# rack_backplane_v9_0.net
KiCad netlist of a schematic drawn in EAGLE
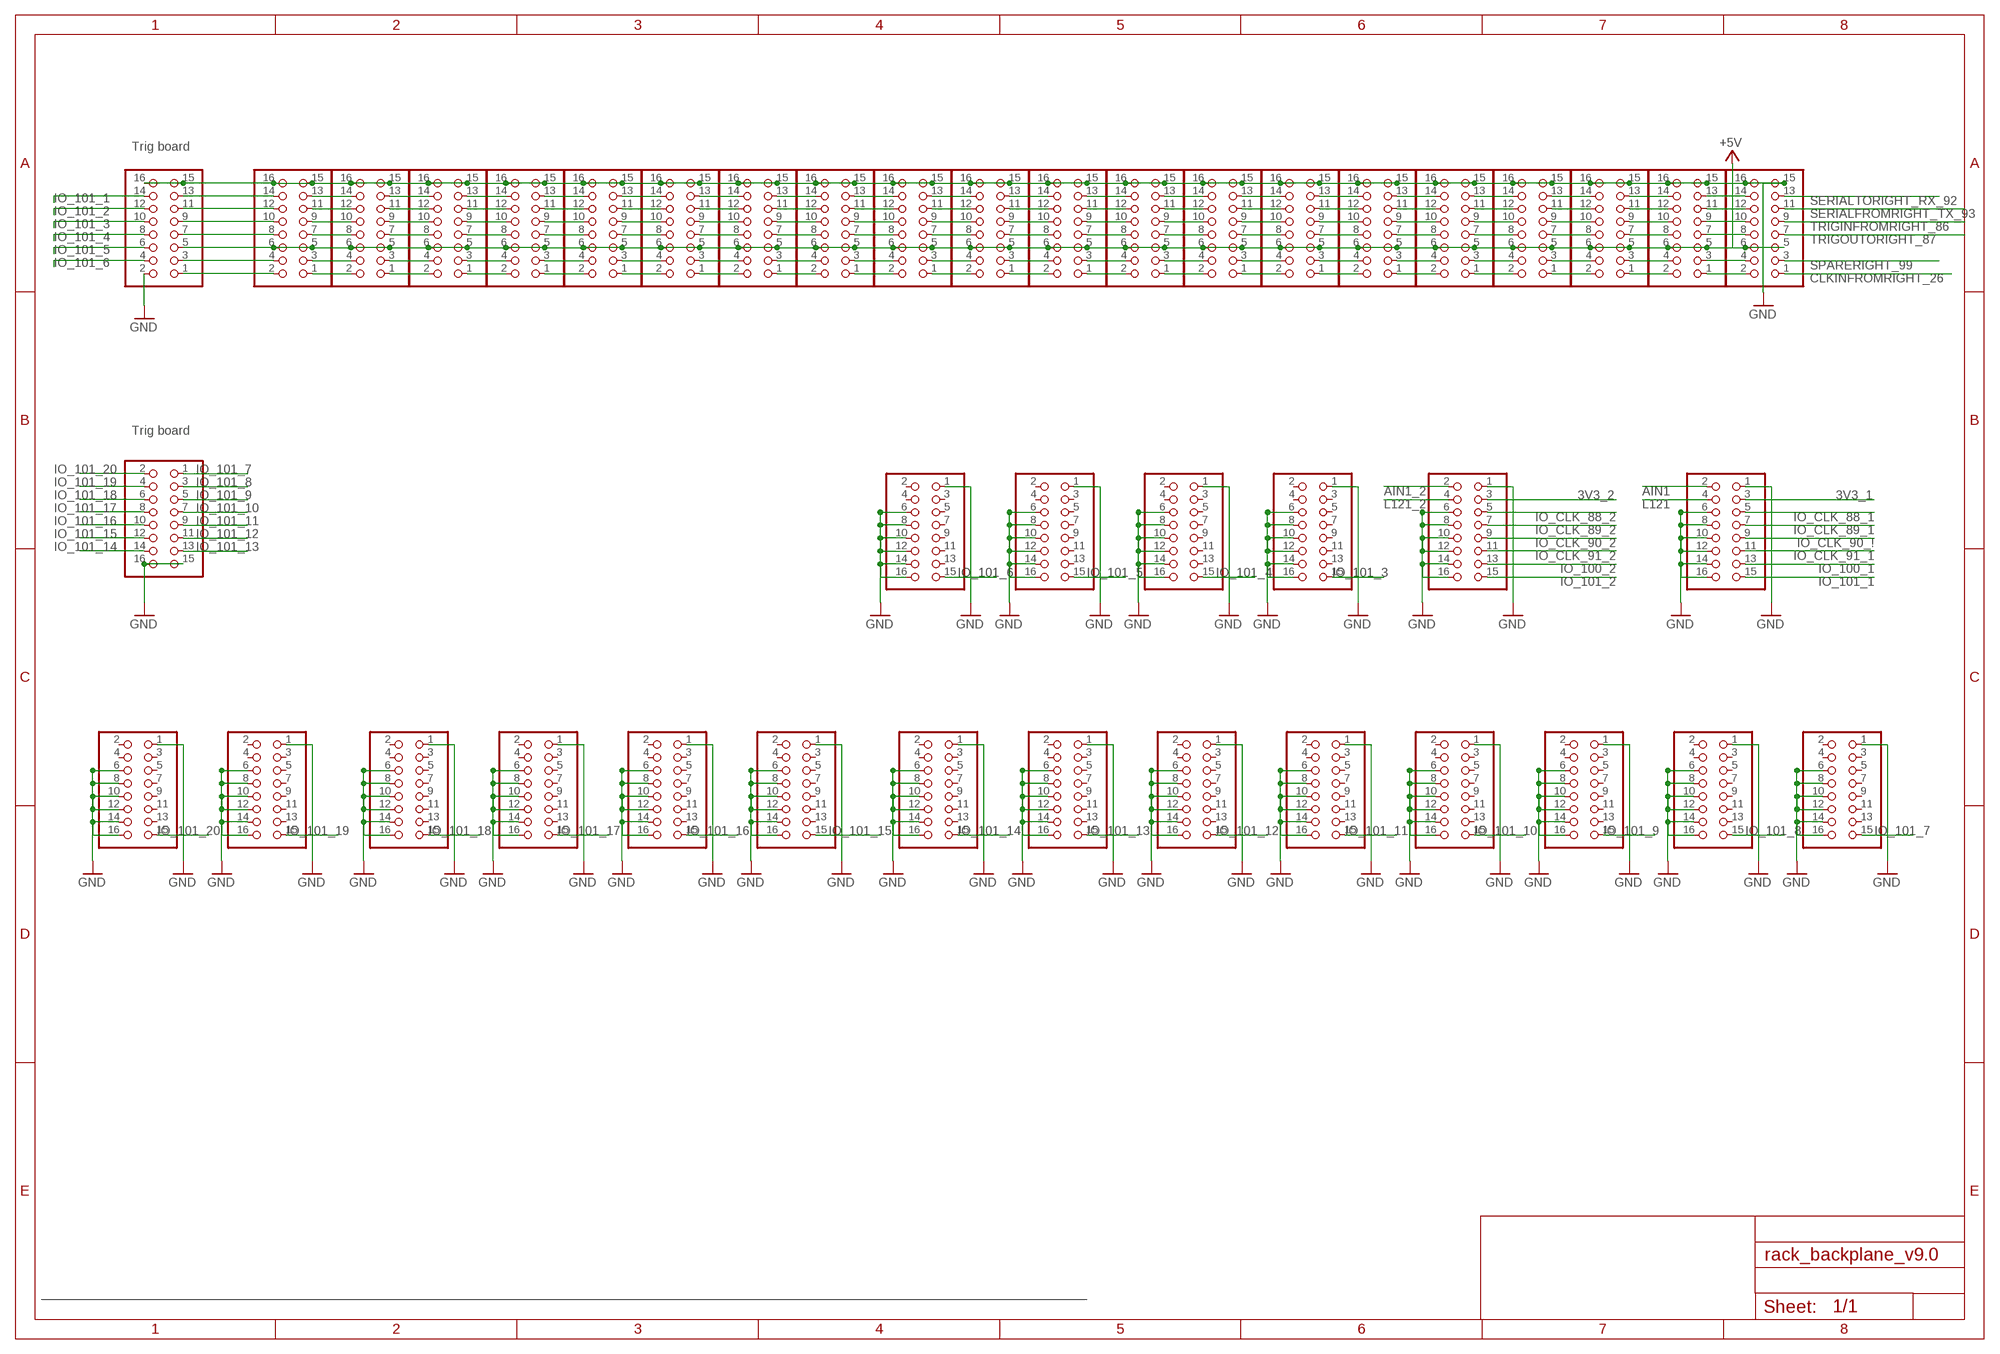
[diagram p0: schematic, sheet 1]

(export (version "E")
  (design (tool "Eeschema 10.0.6"))
  (components
    (comp (ref "PIN_AIN_PWRGND1")
      (value "15-91-2160")
      (footprint "eagle-import:2X08")
      (libsource (lib "eagle-import") (part "PINHD-2X8"))
    )
    (comp (ref "PIN_AIN_PWRGND2")
      (value "15-91-2160")
      (footprint "eagle-import:2X08")
      (libsource (lib "eagle-import") (part "PINHD-2X8"))
    )
    (comp (ref "PIN_AIN_PWRGND3")
      (value "15-91-2160")
      (footprint "eagle-import:2X08")
      (libsource (lib "eagle-import") (part "PINHD-2X8"))
    )
    (comp (ref "PIN_AIN_PWRGND4")
      (value "15-91-2160")
      (footprint "eagle-import:2X08")
      (libsource (lib "eagle-import") (part "PINHD-2X8"))
    )
    (comp (ref "PIN_AIN_PWRGND5")
      (value "15-91-2160")
      (footprint "eagle-import:2X08")
      (libsource (lib "eagle-import") (part "PINHD-2X8"))
    )
    (comp (ref "PIN_AIN_PWRGND6")
      (value "15-91-2160")
      (footprint "eagle-import:2X08")
      (libsource (lib "eagle-import") (part "PINHD-2X8"))
    )
    (comp (ref "PIN_AIN_PWRGND7")
      (value "15-91-2160")
      (footprint "eagle-import:2X08")
      (libsource (lib "eagle-import") (part "PINHD-2X8"))
    )
    (comp (ref "PIN_AIN_PWRGND8")
      (value "15-91-2160")
      (footprint "eagle-import:2X08")
      (libsource (lib "eagle-import") (part "PINHD-2X8"))
    )
    (comp (ref "PIN_AIN_PWRGND9")
      (value "15-91-2160")
      (footprint "eagle-import:2X08")
      (libsource (lib "eagle-import") (part "PINHD-2X8"))
    )
    (comp (ref "PIN_AIN_PWRGND10")
      (value "15-91-2160")
      (footprint "eagle-import:2X08")
      (libsource (lib "eagle-import") (part "PINHD-2X8"))
    )
    (comp (ref "PIN_AIN_PWRGND11")
      (value "15-91-2160")
      (footprint "eagle-import:2X08")
      (libsource (lib "eagle-import") (part "PINHD-2X8"))
    )
    (comp (ref "PIN_AIN_PWRGND12")
      (value "15-91-2160")
      (footprint "eagle-import:2X08")
      (libsource (lib "eagle-import") (part "PINHD-2X8"))
    )
    (comp (ref "PIN_AIN_PWRGND13")
      (value "15-91-2160")
      (footprint "eagle-import:2X08")
      (libsource (lib "eagle-import") (part "PINHD-2X8"))
    )
    (comp (ref "PIN_AIN_PWRGND14")
      (value "15-91-2160")
      (footprint "eagle-import:2X08")
      (libsource (lib "eagle-import") (part "PINHD-2X8"))
    )
    (comp (ref "PIN_AIN_PWRGND15")
      (value "15-91-2160")
      (footprint "eagle-import:2X08")
      (libsource (lib "eagle-import") (part "PINHD-2X8"))
    )
    (comp (ref "PIN_AIN_PWRGND16")
      (value "15-91-2160")
      (footprint "eagle-import:2X08")
      (libsource (lib "eagle-import") (part "PINHD-2X8"))
    )
    (comp (ref "PIN_AIN_PWRGND17")
      (value "15-91-2160")
      (footprint "eagle-import:2X08")
      (libsource (lib "eagle-import") (part "PINHD-2X8"))
    )
    (comp (ref "PIN_AIN_PWRGND18")
      (value "15-91-2160")
      (footprint "eagle-import:2X08")
      (libsource (lib "eagle-import") (part "PINHD-2X8"))
    )
    (comp (ref "PIN_AIN_PWRGND19")
      (value "15-91-2160")
      (footprint "eagle-import:2X08")
      (libsource (lib "eagle-import") (part "PINHD-2X8"))
    )
    (comp (ref "PIN_AIN_PWRGND20")
      (value "15-91-2160")
      (footprint "eagle-import:2X08")
      (libsource (lib "eagle-import") (part "PINHD-2X8"))
    )
    (comp (ref "PIN_AIN_PWRGND21")
      (value "15-91-2160")
      (footprint "eagle-import:2X08")
      (libsource (lib "eagle-import") (part "PINHD-2X8"))
    )
    (comp (ref "PIN_ANALOG_1")
      (value "15-91-2160")
      (footprint "eagle-import:2X08")
      (libsource (lib "eagle-import") (part "PINHD-2X8"))
    )
    (comp (ref "PIN_ANALOG_2")
      (value "15-91-2160")
      (footprint "eagle-import:2X08")
      (libsource (lib "eagle-import") (part "PINHD-2X8"))
    )
    (comp (ref "PIN_ANALOG_3")
      (value "15-91-2160")
      (footprint "eagle-import:2X08")
      (libsource (lib "eagle-import") (part "PINHD-2X8"))
    )
    (comp (ref "PIN_ANALOG_4")
      (value "15-91-2160")
      (footprint "eagle-import:2X08")
      (libsource (lib "eagle-import") (part "PINHD-2X8"))
    )
    (comp (ref "PIN_ANALOG_5")
      (value "15-91-2160")
      (footprint "eagle-import:2X08")
      (libsource (lib "eagle-import") (part "PINHD-2X8"))
    )
    (comp (ref "PIN_ANALOG_6")
      (value "15-91-2160")
      (footprint "eagle-import:2X08")
      (libsource (lib "eagle-import") (part "PINHD-2X8"))
    )
    (comp (ref "PIN_ANALOG_7")
      (value "15-91-2160")
      (footprint "eagle-import:2X08")
      (libsource (lib "eagle-import") (part "PINHD-2X8"))
    )
    (comp (ref "PIN_ANALOG_8")
      (value "15-91-2160")
      (footprint "eagle-import:2X08")
      (libsource (lib "eagle-import") (part "PINHD-2X8"))
    )
    (comp (ref "PIN_ANALOG_9")
      (value "15-91-2160")
      (footprint "eagle-import:2X08")
      (libsource (lib "eagle-import") (part "PINHD-2X8"))
    )
    (comp (ref "PIN_ANALOG_10")
      (value "15-91-2160")
      (footprint "eagle-import:2X08")
      (libsource (lib "eagle-import") (part "PINHD-2X8"))
    )
    (comp (ref "PIN_ANALOG_11")
      (value "15-91-2160")
      (footprint "eagle-import:2X08")
      (libsource (lib "eagle-import") (part "PINHD-2X8"))
    )
    (comp (ref "PIN_ANALOG_12")
      (value "15-91-2160")
      (footprint "eagle-import:2X08")
      (libsource (lib "eagle-import") (part "PINHD-2X8"))
    )
    (comp (ref "PIN_ANALOG_13")
      (value "15-91-2160")
      (footprint "eagle-import:2X08")
      (libsource (lib "eagle-import") (part "PINHD-2X8"))
    )
    (comp (ref "PIN_ANALOG_14")
      (value "15-91-2160")
      (footprint "eagle-import:2X08")
      (libsource (lib "eagle-import") (part "PINHD-2X8"))
    )
    (comp (ref "PIN_ANALOG_15")
      (value "15-91-2160")
      (footprint "eagle-import:2X08")
      (libsource (lib "eagle-import") (part "PINHD-2X8"))
    )
    (comp (ref "PIN_ANALOG_16")
      (value "15-91-2160")
      (footprint "eagle-import:2X08")
      (libsource (lib "eagle-import") (part "PINHD-2X8"))
    )
    (comp (ref "PIN_ANALOG_17")
      (value "15-91-2160")
      (footprint "eagle-import:2X08")
      (libsource (lib "eagle-import") (part "PINHD-2X8"))
    )
    (comp (ref "PIN_ANALOG_18")
      (value "15-91-2160")
      (footprint "eagle-import:2X08")
      (libsource (lib "eagle-import") (part "PINHD-2X8"))
    )
    (comp (ref "PIN_ANALOG_19")
      (value "15-91-2160")
      (footprint "eagle-import:2X08")
      (libsource (lib "eagle-import") (part "PINHD-2X8"))
    )
    (comp (ref "PIN_ANALOG_20")
      (value "15-91-2160")
      (footprint "eagle-import:2X08")
      (libsource (lib "eagle-import") (part "PINHD-2X8"))
    )
    (comp (ref "PIN_ANALOG_21")
      (value "15-91-2160")
      (footprint "eagle-import:2X08")
      (libsource (lib "eagle-import") (part "PINHD-2X8"))
    )
  )
  (nets
    (net (code "1") (name "+5V") (class "Default")
      (node (ref "PIN_ANALOG_1") (pin "5") (pinfunction "5_5") (pintype "passive"))
      (node (ref "PIN_ANALOG_1") (pin "6") (pinfunction "6_6") (pintype "passive"))
      (node (ref "PIN_ANALOG_10") (pin "5") (pinfunction "5_5") (pintype "passive"))
      (node (ref "PIN_ANALOG_10") (pin "6") (pinfunction "6_6") (pintype "passive"))
      (node (ref "PIN_ANALOG_11") (pin "5") (pinfunction "5_5") (pintype "passive"))
      (node (ref "PIN_ANALOG_11") (pin "6") (pinfunction "6_6") (pintype "passive"))
      (node (ref "PIN_ANALOG_12") (pin "5") (pinfunction "5_5") (pintype "passive"))
      (node (ref "PIN_ANALOG_12") (pin "6") (pinfunction "6_6") (pintype "passive"))
      (node (ref "PIN_ANALOG_13") (pin "5") (pinfunction "5_5") (pintype "passive"))
      (node (ref "PIN_ANALOG_13") (pin "6") (pinfunction "6_6") (pintype "passive"))
      (node (ref "PIN_ANALOG_14") (pin "5") (pinfunction "5_5") (pintype "passive"))
      (node (ref "PIN_ANALOG_14") (pin "6") (pinfunction "6_6") (pintype "passive"))
      (node (ref "PIN_ANALOG_15") (pin "5") (pinfunction "5_5") (pintype "passive"))
      (node (ref "PIN_ANALOG_15") (pin "6") (pinfunction "6_6") (pintype "passive"))
      (node (ref "PIN_ANALOG_16") (pin "5") (pinfunction "5_5") (pintype "passive"))
      (node (ref "PIN_ANALOG_16") (pin "6") (pinfunction "6_6") (pintype "passive"))
      (node (ref "PIN_ANALOG_17") (pin "5") (pinfunction "5_5") (pintype "passive"))
      (node (ref "PIN_ANALOG_17") (pin "6") (pinfunction "6_6") (pintype "passive"))
      (node (ref "PIN_ANALOG_18") (pin "5") (pinfunction "5_5") (pintype "passive"))
      (node (ref "PIN_ANALOG_18") (pin "6") (pinfunction "6_6") (pintype "passive"))
      (node (ref "PIN_ANALOG_19") (pin "5") (pinfunction "5_5") (pintype "passive"))
      (node (ref "PIN_ANALOG_19") (pin "6") (pinfunction "6_6") (pintype "passive"))
      (node (ref "PIN_ANALOG_2") (pin "5") (pinfunction "5_5") (pintype "passive"))
      (node (ref "PIN_ANALOG_2") (pin "6") (pinfunction "6_6") (pintype "passive"))
      (node (ref "PIN_ANALOG_20") (pin "5") (pinfunction "5_5") (pintype "passive"))
      (node (ref "PIN_ANALOG_20") (pin "6") (pinfunction "6_6") (pintype "passive"))
      (node (ref "PIN_ANALOG_21") (pin "5") (pinfunction "5_5") (pintype "passive"))
      (node (ref "PIN_ANALOG_3") (pin "5") (pinfunction "5_5") (pintype "passive"))
      (node (ref "PIN_ANALOG_3") (pin "6") (pinfunction "6_6") (pintype "passive"))
      (node (ref "PIN_ANALOG_4") (pin "5") (pinfunction "5_5") (pintype "passive"))
      (node (ref "PIN_ANALOG_4") (pin "6") (pinfunction "6_6") (pintype "passive"))
      (node (ref "PIN_ANALOG_5") (pin "5") (pinfunction "5_5") (pintype "passive"))
      (node (ref "PIN_ANALOG_5") (pin "6") (pinfunction "6_6") (pintype "passive"))
      (node (ref "PIN_ANALOG_6") (pin "5") (pinfunction "5_5") (pintype "passive"))
      (node (ref "PIN_ANALOG_6") (pin "6") (pinfunction "6_6") (pintype "passive"))
      (node (ref "PIN_ANALOG_7") (pin "5") (pinfunction "5_5") (pintype "passive"))
      (node (ref "PIN_ANALOG_7") (pin "6") (pinfunction "6_6") (pintype "passive"))
      (node (ref "PIN_ANALOG_8") (pin "5") (pinfunction "5_5") (pintype "passive"))
      (node (ref "PIN_ANALOG_8") (pin "6") (pinfunction "6_6") (pintype "passive"))
      (node (ref "PIN_ANALOG_9") (pin "5") (pinfunction "5_5") (pintype "passive"))
      (node (ref "PIN_ANALOG_9") (pin "6") (pinfunction "6_6") (pintype "passive"))
    )
    (net (code "2") (name "/3V3_1") (class "Default")
      (node (ref "PIN_AIN_PWRGND1") (pin "3") (pinfunction "3_3") (pintype "passive"))
    )
    (net (code "3") (name "/3V3_2") (class "Default")
      (node (ref "PIN_AIN_PWRGND2") (pin "3") (pinfunction "3_3") (pintype "passive"))
    )
    (net (code "4") (name "/AIN1") (class "Default")
      (node (ref "PIN_AIN_PWRGND1") (pin "2") (pinfunction "2_2") (pintype "passive"))
    )
    (net (code "5") (name "/AIN1_2") (class "Default")
      (node (ref "PIN_AIN_PWRGND2") (pin "2") (pinfunction "2_2") (pintype "passive"))
    )
    (net (code "6") (name "/CLKINFROMRIGHT_26") (class "Default")
      (node (ref "PIN_ANALOG_1") (pin "1") (pinfunction "1_1") (pintype "passive"))
    )
    (net (code "7") (name "/IO_100_1") (class "Default")
      (node (ref "PIN_AIN_PWRGND1") (pin "13") (pinfunction "13_13") (pintype "passive"))
    )
    (net (code "8") (name "/IO_100_2") (class "Default")
      (node (ref "PIN_AIN_PWRGND2") (pin "13") (pinfunction "13_13") (pintype "passive"))
    )
    (net (code "9") (name "/IO_101_1") (class "Default")
      (node (ref "PIN_AIN_PWRGND1") (pin "15") (pinfunction "15_15") (pintype "passive"))
      (node (ref "PIN_ANALOG_21") (pin "14") (pinfunction "14_14") (pintype "passive"))
    )
    (net (code "10") (name "/IO_101_2") (class "Default")
      (node (ref "PIN_AIN_PWRGND2") (pin "15") (pinfunction "15_15") (pintype "passive"))
      (node (ref "PIN_ANALOG_21") (pin "12") (pinfunction "12_12") (pintype "passive"))
    )
    (net (code "11") (name "/IO_101_3") (class "Default")
      (node (ref "PIN_AIN_PWRGND3") (pin "15") (pinfunction "15_15") (pintype "passive"))
      (node (ref "PIN_ANALOG_21") (pin "10") (pinfunction "10_10") (pintype "passive"))
    )
    (net (code "12") (name "/IO_101_4") (class "Default")
      (node (ref "PIN_AIN_PWRGND4") (pin "15") (pinfunction "15_15") (pintype "passive"))
      (node (ref "PIN_ANALOG_21") (pin "8") (pinfunction "8_8") (pintype "passive"))
    )
    (net (code "13") (name "/IO_101_5") (class "Default")
      (node (ref "PIN_AIN_PWRGND5") (pin "15") (pinfunction "15_15") (pintype "passive"))
      (node (ref "PIN_ANALOG_21") (pin "6") (pinfunction "6_6") (pintype "passive"))
    )
    (net (code "14") (name "/IO_101_6") (class "Default")
      (node (ref "PIN_AIN_PWRGND6") (pin "15") (pinfunction "15_15") (pintype "passive"))
      (node (ref "PIN_ANALOG_21") (pin "4") (pinfunction "4_4") (pintype "passive"))
    )
    (net (code "15") (name "/IO_101_7") (class "Default")
      (node (ref "PIN_AIN_PWRGND21") (pin "1") (pinfunction "1_1") (pintype "passive"))
      (node (ref "PIN_AIN_PWRGND7") (pin "15") (pinfunction "15_15") (pintype "passive"))
    )
    (net (code "16") (name "/IO_101_8") (class "Default")
      (node (ref "PIN_AIN_PWRGND21") (pin "3") (pinfunction "3_3") (pintype "passive"))
      (node (ref "PIN_AIN_PWRGND8") (pin "15") (pinfunction "15_15") (pintype "passive"))
    )
    (net (code "17") (name "/IO_101_9") (class "Default")
      (node (ref "PIN_AIN_PWRGND21") (pin "5") (pinfunction "5_5") (pintype "passive"))
      (node (ref "PIN_AIN_PWRGND9") (pin "15") (pinfunction "15_15") (pintype "passive"))
    )
    (net (code "18") (name "/IO_101_10") (class "Default")
      (node (ref "PIN_AIN_PWRGND10") (pin "15") (pinfunction "15_15") (pintype "passive"))
      (node (ref "PIN_AIN_PWRGND21") (pin "7") (pinfunction "7_7") (pintype "passive"))
    )
    (net (code "19") (name "/IO_101_11") (class "Default")
      (node (ref "PIN_AIN_PWRGND11") (pin "15") (pinfunction "15_15") (pintype "passive"))
      (node (ref "PIN_AIN_PWRGND21") (pin "9") (pinfunction "9_9") (pintype "passive"))
    )
    (net (code "20") (name "/IO_101_12") (class "Default")
      (node (ref "PIN_AIN_PWRGND12") (pin "15") (pinfunction "15_15") (pintype "passive"))
      (node (ref "PIN_AIN_PWRGND21") (pin "11") (pinfunction "11_11") (pintype "passive"))
    )
    (net (code "21") (name "/IO_101_13") (class "Default")
      (node (ref "PIN_AIN_PWRGND13") (pin "15") (pinfunction "15_15") (pintype "passive"))
      (node (ref "PIN_AIN_PWRGND21") (pin "13") (pinfunction "13_13") (pintype "passive"))
    )
    (net (code "22") (name "/IO_101_14") (class "Default")
      (node (ref "PIN_AIN_PWRGND14") (pin "15") (pinfunction "15_15") (pintype "passive"))
      (node (ref "PIN_AIN_PWRGND21") (pin "14") (pinfunction "14_14") (pintype "passive"))
    )
    (net (code "23") (name "/IO_101_15") (class "Default")
      (node (ref "PIN_AIN_PWRGND15") (pin "15") (pinfunction "15_15") (pintype "passive"))
      (node (ref "PIN_AIN_PWRGND21") (pin "12") (pinfunction "12_12") (pintype "passive"))
    )
    (net (code "24") (name "/IO_101_16") (class "Default")
      (node (ref "PIN_AIN_PWRGND16") (pin "15") (pinfunction "15_15") (pintype "passive"))
      (node (ref "PIN_AIN_PWRGND21") (pin "10") (pinfunction "10_10") (pintype "passive"))
    )
    (net (code "25") (name "/IO_101_17") (class "Default")
      (node (ref "PIN_AIN_PWRGND17") (pin "15") (pinfunction "15_15") (pintype "passive"))
      (node (ref "PIN_AIN_PWRGND21") (pin "8") (pinfunction "8_8") (pintype "passive"))
    )
    (net (code "26") (name "/IO_101_18") (class "Default")
      (node (ref "PIN_AIN_PWRGND18") (pin "15") (pinfunction "15_15") (pintype "passive"))
      (node (ref "PIN_AIN_PWRGND21") (pin "6") (pinfunction "6_6") (pintype "passive"))
    )
    (net (code "27") (name "/IO_101_19") (class "Default")
      (node (ref "PIN_AIN_PWRGND19") (pin "15") (pinfunction "15_15") (pintype "passive"))
      (node (ref "PIN_AIN_PWRGND21") (pin "4") (pinfunction "4_4") (pintype "passive"))
    )
    (net (code "28") (name "/IO_101_20") (class "Default")
      (node (ref "PIN_AIN_PWRGND20") (pin "15") (pinfunction "15_15") (pintype "passive"))
      (node (ref "PIN_AIN_PWRGND21") (pin "2") (pinfunction "2_2") (pintype "passive"))
    )
    (net (code "29") (name "/IO_CLK_88_1") (class "Default")
      (node (ref "PIN_AIN_PWRGND1") (pin "5") (pinfunction "5_5") (pintype "passive"))
    )
    (net (code "30") (name "/IO_CLK_88_2") (class "Default")
      (node (ref "PIN_AIN_PWRGND2") (pin "5") (pinfunction "5_5") (pintype "passive"))
    )
    (net (code "31") (name "/IO_CLK_89_1") (class "Default")
      (node (ref "PIN_AIN_PWRGND1") (pin "7") (pinfunction "7_7") (pintype "passive"))
    )
    (net (code "32") (name "/IO_CLK_89_2") (class "Default")
      (node (ref "PIN_AIN_PWRGND2") (pin "7") (pinfunction "7_7") (pintype "passive"))
    )
    (net (code "33") (name "/IO_CLK_90_2") (class "Default")
      (node (ref "PIN_AIN_PWRGND2") (pin "9") (pinfunction "9_9") (pintype "passive"))
    )
    (net (code "34") (name "/IO_CLK_90_~{}") (class "Default")
      (node (ref "PIN_AIN_PWRGND1") (pin "9") (pinfunction "9_9") (pintype "passive"))
    )
    (net (code "35") (name "/IO_CLK_91_1") (class "Default")
      (node (ref "PIN_AIN_PWRGND1") (pin "11") (pinfunction "11_11") (pintype "passive"))
    )
    (net (code "36") (name "/IO_CLK_91_2") (class "Default")
      (node (ref "PIN_AIN_PWRGND2") (pin "11") (pinfunction "11_11") (pintype "passive"))
    )
    (net (code "37") (name "/L121") (class "Default")
      (node (ref "PIN_AIN_PWRGND1") (pin "4") (pinfunction "4_4") (pintype "passive"))
    )
    (net (code "38") (name "/L121_2") (class "Default")
      (node (ref "PIN_AIN_PWRGND2") (pin "4") (pinfunction "4_4") (pintype "passive"))
    )
    (net (code "39") (name "/SERIALFROMRIGHT_TX_93") (class "Default")
      (node (ref "PIN_ANALOG_1") (pin "11") (pinfunction "11_11") (pintype "passive"))
    )
    (net (code "40") (name "/SERIALTORIGHT_RX_92") (class "Default")
      (node (ref "PIN_ANALOG_1") (pin "13") (pinfunction "13_13") (pintype "passive"))
    )
    (net (code "41") (name "/SPARERIGHT_99") (class "Default")
      (node (ref "PIN_ANALOG_1") (pin "3") (pinfunction "3_3") (pintype "passive"))
    )
    (net (code "42") (name "/TRIGINFROMRIGHT_86") (class "Default")
      (node (ref "PIN_ANALOG_1") (pin "9") (pinfunction "9_9") (pintype "passive"))
    )
    (net (code "43") (name "/TRIGOUTORIGHT_87") (class "Default")
      (node (ref "PIN_ANALOG_1") (pin "7") (pinfunction "7_7") (pintype "passive"))
    )
    (net (code "44") (name "GND") (class "Default")
      (node (ref "PIN_AIN_PWRGND1") (pin "1") (pinfunction "1_1") (pintype "passive"))
      (node (ref "PIN_AIN_PWRGND1") (pin "10") (pinfunction "10_10") (pintype "passive"))
      (node (ref "PIN_AIN_PWRGND1") (pin "12") (pinfunction "12_12") (pintype "passive"))
      (node (ref "PIN_AIN_PWRGND1") (pin "14") (pinfunction "14_14") (pintype "passive"))
      (node (ref "PIN_AIN_PWRGND1") (pin "16") (pinfunction "16_16") (pintype "passive"))
      (node (ref "PIN_AIN_PWRGND1") (pin "6") (pinfunction "6_6") (pintype "passive"))
      (node (ref "PIN_AIN_PWRGND1") (pin "8") (pinfunction "8_8") (pintype "passive"))
      (node (ref "PIN_AIN_PWRGND10") (pin "1") (pinfunction "1_1") (pintype "passive"))
      (node (ref "PIN_AIN_PWRGND10") (pin "10") (pinfunction "10_10") (pintype "passive"))
      (node (ref "PIN_AIN_PWRGND10") (pin "12") (pinfunction "12_12") (pintype "passive"))
      (node (ref "PIN_AIN_PWRGND10") (pin "14") (pinfunction "14_14") (pintype "passive"))
      (node (ref "PIN_AIN_PWRGND10") (pin "16") (pinfunction "16_16") (pintype "passive"))
      (node (ref "PIN_AIN_PWRGND10") (pin "6") (pinfunction "6_6") (pintype "passive"))
      (node (ref "PIN_AIN_PWRGND10") (pin "8") (pinfunction "8_8") (pintype "passive"))
      (node (ref "PIN_AIN_PWRGND11") (pin "1") (pinfunction "1_1") (pintype "passive"))
      (node (ref "PIN_AIN_PWRGND11") (pin "10") (pinfunction "10_10") (pintype "passive"))
      (node (ref "PIN_AIN_PWRGND11") (pin "12") (pinfunction "12_12") (pintype "passive"))
      (node (ref "PIN_AIN_PWRGND11") (pin "14") (pinfunction "14_14") (pintype "passive"))
      (node (ref "PIN_AIN_PWRGND11") (pin "16") (pinfunction "16_16") (pintype "passive"))
      (node (ref "PIN_AIN_PWRGND11") (pin "6") (pinfunction "6_6") (pintype "passive"))
      (node (ref "PIN_AIN_PWRGND11") (pin "8") (pinfunction "8_8") (pintype "passive"))
      (node (ref "PIN_AIN_PWRGND12") (pin "1") (pinfunction "1_1") (pintype "passive"))
      (node (ref "PIN_AIN_PWRGND12") (pin "10") (pinfunction "10_10") (pintype "passive"))
      (node (ref "PIN_AIN_PWRGND12") (pin "12") (pinfunction "12_12") (pintype "passive"))
      (node (ref "PIN_AIN_PWRGND12") (pin "14") (pinfunction "14_14") (pintype "passive"))
      (node (ref "PIN_AIN_PWRGND12") (pin "16") (pinfunction "16_16") (pintype "passive"))
      (node (ref "PIN_AIN_PWRGND12") (pin "6") (pinfunction "6_6") (pintype "passive"))
      (node (ref "PIN_AIN_PWRGND12") (pin "8") (pinfunction "8_8") (pintype "passive"))
      (node (ref "PIN_AIN_PWRGND13") (pin "1") (pinfunction "1_1") (pintype "passive"))
      (node (ref "PIN_AIN_PWRGND13") (pin "10") (pinfunction "10_10") (pintype "passive"))
      (node (ref "PIN_AIN_PWRGND13") (pin "12") (pinfunction "12_12") (pintype "passive"))
      (node (ref "PIN_AIN_PWRGND13") (pin "14") (pinfunction "14_14") (pintype "passive"))
      (node (ref "PIN_AIN_PWRGND13") (pin "16") (pinfunction "16_16") (pintype "passive"))
      (node (ref "PIN_AIN_PWRGND13") (pin "6") (pinfunction "6_6") (pintype "passive"))
      (node (ref "PIN_AIN_PWRGND13") (pin "8") (pinfunction "8_8") (pintype "passive"))
      (node (ref "PIN_AIN_PWRGND14") (pin "1") (pinfunction "1_1") (pintype "passive"))
      (node (ref "PIN_AIN_PWRGND14") (pin "10") (pinfunction "10_10") (pintype "passive"))
      (node (ref "PIN_AIN_PWRGND14") (pin "12") (pinfunction "12_12") (pintype "passive"))
      (node (ref "PIN_AIN_PWRGND14") (pin "14") (pinfunction "14_14") (pintype "passive"))
      (node (ref "PIN_AIN_PWRGND14") (pin "16") (pinfunction "16_16") (pintype "passive"))
      (node (ref "PIN_AIN_PWRGND14") (pin "6") (pinfunction "6_6") (pintype "passive"))
      (node (ref "PIN_AIN_PWRGND14") (pin "8") (pinfunction "8_8") (pintype "passive"))
      (node (ref "PIN_AIN_PWRGND15") (pin "1") (pinfunction "1_1") (pintype "passive"))
      (node (ref "PIN_AIN_PWRGND15") (pin "10") (pinfunction "10_10") (pintype "passive"))
      (node (ref "PIN_AIN_PWRGND15") (pin "12") (pinfunction "12_12") (pintype "passive"))
      (node (ref "PIN_AIN_PWRGND15") (pin "14") (pinfunction "14_14") (pintype "passive"))
      (node (ref "PIN_AIN_PWRGND15") (pin "16") (pinfunction "16_16") (pintype "passive"))
      (node (ref "PIN_AIN_PWRGND15") (pin "6") (pinfunction "6_6") (pintype "passive"))
      (node (ref "PIN_AIN_PWRGND15") (pin "8") (pinfunction "8_8") (pintype "passive"))
      (node (ref "PIN_AIN_PWRGND16") (pin "1") (pinfunction "1_1") (pintype "passive"))
      (node (ref "PIN_AIN_PWRGND16") (pin "10") (pinfunction "10_10") (pintype "passive"))
      (node (ref "PIN_AIN_PWRGND16") (pin "12") (pinfunction "12_12") (pintype "passive"))
      (node (ref "PIN_AIN_PWRGND16") (pin "14") (pinfunction "14_14") (pintype "passive"))
      (node (ref "PIN_AIN_PWRGND16") (pin "16") (pinfunction "16_16") (pintype "passive"))
      (node (ref "PIN_AIN_PWRGND16") (pin "6") (pinfunction "6_6") (pintype "passive"))
      (node (ref "PIN_AIN_PWRGND16") (pin "8") (pinfunction "8_8") (pintype "passive"))
      (node (ref "PIN_AIN_PWRGND17") (pin "1") (pinfunction "1_1") (pintype "passive"))
      (node (ref "PIN_AIN_PWRGND17") (pin "10") (pinfunction "10_10") (pintype "passive"))
      (node (ref "PIN_AIN_PWRGND17") (pin "12") (pinfunction "12_12") (pintype "passive"))
      (node (ref "PIN_AIN_PWRGND17") (pin "14") (pinfunction "14_14") (pintype "passive"))
      (node (ref "PIN_AIN_PWRGND17") (pin "16") (pinfunction "16_16") (pintype "passive"))
      (node (ref "PIN_AIN_PWRGND17") (pin "6") (pinfunction "6_6") (pintype "passive"))
      (node (ref "PIN_AIN_PWRGND17") (pin "8") (pinfunction "8_8") (pintype "passive"))
      (node (ref "PIN_AIN_PWRGND18") (pin "1") (pinfunction "1_1") (pintype "passive"))
      (node (ref "PIN_AIN_PWRGND18") (pin "10") (pinfunction "10_10") (pintype "passive"))
      (node (ref "PIN_AIN_PWRGND18") (pin "12") (pinfunction "12_12") (pintype "passive"))
      (node (ref "PIN_AIN_PWRGND18") (pin "14") (pinfunction "14_14") (pintype "passive"))
      (node (ref "PIN_AIN_PWRGND18") (pin "16") (pinfunction "16_16") (pintype "passive"))
      (node (ref "PIN_AIN_PWRGND18") (pin "6") (pinfunction "6_6") (pintype "passive"))
      (node (ref "PIN_AIN_PWRGND18") (pin "8") (pinfunction "8_8") (pintype "passive"))
      (node (ref "PIN_AIN_PWRGND19") (pin "1") (pinfunction "1_1") (pintype "passive"))
      (node (ref "PIN_AIN_PWRGND19") (pin "10") (pinfunction "10_10") (pintype "passive"))
      (node (ref "PIN_AIN_PWRGND19") (pin "12") (pinfunction "12_12") (pintype "passive"))
      (node (ref "PIN_AIN_PWRGND19") (pin "14") (pinfunction "14_14") (pintype "passive"))
      (node (ref "PIN_AIN_PWRGND19") (pin "16") (pinfunction "16_16") (pintype "passive"))
      (node (ref "PIN_AIN_PWRGND19") (pin "6") (pinfunction "6_6") (pintype "passive"))
      (node (ref "PIN_AIN_PWRGND19") (pin "8") (pinfunction "8_8") (pintype "passive"))
      (node (ref "PIN_AIN_PWRGND2") (pin "1") (pinfunction "1_1") (pintype "passive"))
      (node (ref "PIN_AIN_PWRGND2") (pin "10") (pinfunction "10_10") (pintype "passive"))
      (node (ref "PIN_AIN_PWRGND2") (pin "12") (pinfunction "12_12") (pintype "passive"))
      (node (ref "PIN_AIN_PWRGND2") (pin "14") (pinfunction "14_14") (pintype "passive"))
      (node (ref "PIN_AIN_PWRGND2") (pin "16") (pinfunction "16_16") (pintype "passive"))
      (node (ref "PIN_AIN_PWRGND2") (pin "6") (pinfunction "6_6") (pintype "passive"))
      (node (ref "PIN_AIN_PWRGND2") (pin "8") (pinfunction "8_8") (pintype "passive"))
      (node (ref "PIN_AIN_PWRGND20") (pin "1") (pinfunction "1_1") (pintype "passive"))
      (node (ref "PIN_AIN_PWRGND20") (pin "10") (pinfunction "10_10") (pintype "passive"))
      (node (ref "PIN_AIN_PWRGND20") (pin "12") (pinfunction "12_12") (pintype "passive"))
      (node (ref "PIN_AIN_PWRGND20") (pin "14") (pinfunction "14_14") (pintype "passive"))
      (node (ref "PIN_AIN_PWRGND20") (pin "16") (pinfunction "16_16") (pintype "passive"))
      (node (ref "PIN_AIN_PWRGND20") (pin "6") (pinfunction "6_6") (pintype "passive"))
      (node (ref "PIN_AIN_PWRGND20") (pin "8") (pinfunction "8_8") (pintype "passive"))
      (node (ref "PIN_AIN_PWRGND21") (pin "15") (pinfunction "15_15") (pintype "passive"))
      (node (ref "PIN_AIN_PWRGND21") (pin "16") (pinfunction "16_16") (pintype "passive"))
      (node (ref "PIN_AIN_PWRGND3") (pin "1") (pinfunction "1_1") (pintype "passive"))
      (node (ref "PIN_AIN_PWRGND3") (pin "10") (pinfunction "10_10") (pintype "passive"))
      (node (ref "PIN_AIN_PWRGND3") (pin "12") (pinfunction "12_12") (pintype "passive"))
      (node (ref "PIN_AIN_PWRGND3") (pin "14") (pinfunction "14_14") (pintype "passive"))
      (node (ref "PIN_AIN_PWRGND3") (pin "16") (pinfunction "16_16") (pintype "passive"))
      (node (ref "PIN_AIN_PWRGND3") (pin "6") (pinfunction "6_6") (pintype "passive"))
      (node (ref "PIN_AIN_PWRGND3") (pin "8") (pinfunction "8_8") (pintype "passive"))
      (node (ref "PIN_AIN_PWRGND4") (pin "1") (pinfunction "1_1") (pintype "passive"))
      (node (ref "PIN_AIN_PWRGND4") (pin "10") (pinfunction "10_10") (pintype "passive"))
      (node (ref "PIN_AIN_PWRGND4") (pin "12") (pinfunction "12_12") (pintype "passive"))
      (node (ref "PIN_AIN_PWRGND4") (pin "14") (pinfunction "14_14") (pintype "passive"))
      (node (ref "PIN_AIN_PWRGND4") (pin "16") (pinfunction "16_16") (pintype "passive"))
      (node (ref "PIN_AIN_PWRGND4") (pin "6") (pinfunction "6_6") (pintype "passive"))
      (node (ref "PIN_AIN_PWRGND4") (pin "8") (pinfunction "8_8") (pintype "passive"))
      (node (ref "PIN_AIN_PWRGND5") (pin "1") (pinfunction "1_1") (pintype "passive"))
      (node (ref "PIN_AIN_PWRGND5") (pin "10") (pinfunction "10_10") (pintype "passive"))
      (node (ref "PIN_AIN_PWRGND5") (pin "12") (pinfunction "12_12") (pintype "passive"))
      (node (ref "PIN_AIN_PWRGND5") (pin "14") (pinfunction "14_14") (pintype "passive"))
      (node (ref "PIN_AIN_PWRGND5") (pin "16") (pinfunction "16_16") (pintype "passive"))
      (node (ref "PIN_AIN_PWRGND5") (pin "6") (pinfunction "6_6") (pintype "passive"))
      (node (ref "PIN_AIN_PWRGND5") (pin "8") (pinfunction "8_8") (pintype "passive"))
      (node (ref "PIN_AIN_PWRGND6") (pin "1") (pinfunction "1_1") (pintype "passive"))
      (node (ref "PIN_AIN_PWRGND6") (pin "10") (pinfunction "10_10") (pintype "passive"))
      (node (ref "PIN_AIN_PWRGND6") (pin "12") (pinfunction "12_12") (pintype "passive"))
      (node (ref "PIN_AIN_PWRGND6") (pin "14") (pinfunction "14_14") (pintype "passive"))
      (node (ref "PIN_AIN_PWRGND6") (pin "16") (pinfunction "16_16") (pintype "passive"))
      (node (ref "PIN_AIN_PWRGND6") (pin "6") (pinfunction "6_6") (pintype "passive"))
      (node (ref "PIN_AIN_PWRGND6") (pin "8") (pinfunction "8_8") (pintype "passive"))
      (node (ref "PIN_AIN_PWRGND7") (pin "1") (pinfunction "1_1") (pintype "passive"))
      (node (ref "PIN_AIN_PWRGND7") (pin "10") (pinfunction "10_10") (pintype "passive"))
      (node (ref "PIN_AIN_PWRGND7") (pin "12") (pinfunction "12_12") (pintype "passive"))
      (node (ref "PIN_AIN_PWRGND7") (pin "14") (pinfunction "14_14") (pintype "passive"))
      (node (ref "PIN_AIN_PWRGND7") (pin "16") (pinfunction "16_16") (pintype "passive"))
      (node (ref "PIN_AIN_PWRGND7") (pin "6") (pinfunction "6_6") (pintype "passive"))
      (node (ref "PIN_AIN_PWRGND7") (pin "8") (pinfunction "8_8") (pintype "passive"))
      (node (ref "PIN_AIN_PWRGND8") (pin "1") (pinfunction "1_1") (pintype "passive"))
      (node (ref "PIN_AIN_PWRGND8") (pin "10") (pinfunction "10_10") (pintype "passive"))
      (node (ref "PIN_AIN_PWRGND8") (pin "12") (pinfunction "12_12") (pintype "passive"))
      (node (ref "PIN_AIN_PWRGND8") (pin "14") (pinfunction "14_14") (pintype "passive"))
      (node (ref "PIN_AIN_PWRGND8") (pin "16") (pinfunction "16_16") (pintype "passive"))
      (node (ref "PIN_AIN_PWRGND8") (pin "6") (pinfunction "6_6") (pintype "passive"))
      (node (ref "PIN_AIN_PWRGND8") (pin "8") (pinfunction "8_8") (pintype "passive"))
      (node (ref "PIN_AIN_PWRGND9") (pin "1") (pinfunction "1_1") (pintype "passive"))
      (node (ref "PIN_AIN_PWRGND9") (pin "10") (pinfunction "10_10") (pintype "passive"))
      (node (ref "PIN_AIN_PWRGND9") (pin "12") (pinfunction "12_12") (pintype "passive"))
      (node (ref "PIN_AIN_PWRGND9") (pin "14") (pinfunction "14_14") (pintype "passive"))
      (node (ref "PIN_AIN_PWRGND9") (pin "16") (pinfunction "16_16") (pintype "passive"))
      (node (ref "PIN_AIN_PWRGND9") (pin "6") (pinfunction "6_6") (pintype "passive"))
      (node (ref "PIN_AIN_PWRGND9") (pin "8") (pinfunction "8_8") (pintype "passive"))
      (node (ref "PIN_ANALOG_1") (pin "15") (pinfunction "15_15") (pintype "passive"))
      (node (ref "PIN_ANALOG_1") (pin "16") (pinfunction "16_16") (pintype "passive"))
      (node (ref "PIN_ANALOG_10") (pin "15") (pinfunction "15_15") (pintype "passive"))
      (node (ref "PIN_ANALOG_10") (pin "16") (pinfunction "16_16") (pintype "passive"))
      (node (ref "PIN_ANALOG_11") (pin "15") (pinfunction "15_15") (pintype "passive"))
      (node (ref "PIN_ANALOG_11") (pin "16") (pinfunction "16_16") (pintype "passive"))
      (node (ref "PIN_ANALOG_12") (pin "15") (pinfunction "15_15") (pintype "passive"))
      (node (ref "PIN_ANALOG_12") (pin "16") (pinfunction "16_16") (pintype "passive"))
      (node (ref "PIN_ANALOG_13") (pin "15") (pinfunction "15_15") (pintype "passive"))
      (node (ref "PIN_ANALOG_13") (pin "16") (pinfunction "16_16") (pintype "passive"))
      (node (ref "PIN_ANALOG_14") (pin "15") (pinfunction "15_15") (pintype "passive"))
      (node (ref "PIN_ANALOG_14") (pin "16") (pinfunction "16_16") (pintype "passive"))
      (node (ref "PIN_ANALOG_15") (pin "15") (pinfunction "15_15") (pintype "passive"))
      (node (ref "PIN_ANALOG_15") (pin "16") (pinfunction "16_16") (pintype "passive"))
      (node (ref "PIN_ANALOG_16") (pin "15") (pinfunction "15_15") (pintype "passive"))
      (node (ref "PIN_ANALOG_16") (pin "16") (pinfunction "16_16") (pintype "passive"))
      (node (ref "PIN_ANALOG_17") (pin "15") (pinfunction "15_15") (pintype "passive"))
      (node (ref "PIN_ANALOG_17") (pin "16") (pinfunction "16_16") (pintype "passive"))
      (node (ref "PIN_ANALOG_18") (pin "15") (pinfunction "15_15") (pintype "passive"))
      (node (ref "PIN_ANALOG_18") (pin "16") (pinfunction "16_16") (pintype "passive"))
      (node (ref "PIN_ANALOG_19") (pin "15") (pinfunction "15_15") (pintype "passive"))
      (node (ref "PIN_ANALOG_19") (pin "16") (pinfunction "16_16") (pintype "passive"))
      (node (ref "PIN_ANALOG_2") (pin "15") (pinfunction "15_15") (pintype "passive"))
      (node (ref "PIN_ANALOG_2") (pin "16") (pinfunction "16_16") (pintype "passive"))
      (node (ref "PIN_ANALOG_20") (pin "15") (pinfunction "15_15") (pintype "passive"))
      (node (ref "PIN_ANALOG_20") (pin "16") (pinfunction "16_16") (pintype "passive"))
      (node (ref "PIN_ANALOG_21") (pin "15") (pinfunction "15_15") (pintype "passive"))
      (node (ref "PIN_ANALOG_21") (pin "16") (pinfunction "16_16") (pintype "passive"))
      (node (ref "PIN_ANALOG_21") (pin "2") (pinfunction "2_2") (pintype "passive"))
      (node (ref "PIN_ANALOG_3") (pin "15") (pinfunction "15_15") (pintype "passive"))
      (node (ref "PIN_ANALOG_3") (pin "16") (pinfunction "16_16") (pintype "passive"))
      (node (ref "PIN_ANALOG_4") (pin "15") (pinfunction "15_15") (pintype "passive"))
      (node (ref "PIN_ANALOG_4") (pin "16") (pinfunction "16_16") (pintype "passive"))
      (node (ref "PIN_ANALOG_5") (pin "15") (pinfunction "15_15") (pintype "passive"))
      (node (ref "PIN_ANALOG_5") (pin "16") (pinfunction "16_16") (pintype "passive"))
      (node (ref "PIN_ANALOG_6") (pin "15") (pinfunction "15_15") (pintype "passive"))
      (node (ref "PIN_ANALOG_6") (pin "16") (pinfunction "16_16") (pintype "passive"))
      (node (ref "PIN_ANALOG_7") (pin "15") (pinfunction "15_15") (pintype "passive"))
      (node (ref "PIN_ANALOG_7") (pin "16") (pinfunction "16_16") (pintype "passive"))
      (node (ref "PIN_ANALOG_8") (pin "15") (pinfunction "15_15") (pintype "passive"))
      (node (ref "PIN_ANALOG_8") (pin "16") (pinfunction "16_16") (pintype "passive"))
      (node (ref "PIN_ANALOG_9") (pin "15") (pinfunction "15_15") (pintype "passive"))
      (node (ref "PIN_ANALOG_9") (pin "16") (pinfunction "16_16") (pintype "passive"))
    )
    (net (code "45") (name "Net-(PIN_ANALOG_1-Pad2)") (class "Default")
      (node (ref "PIN_ANALOG_1") (pin "2") (pinfunction "2_2") (pintype "passive"))
      (node (ref "PIN_ANALOG_2") (pin "1") (pinfunction "1_1") (pintype "passive"))
    )
    (net (code "46") (name "Net-(PIN_ANALOG_1-Pad4)") (class "Default")
      (node (ref "PIN_ANALOG_1") (pin "4") (pinfunction "4_4") (pintype "passive"))
      (node (ref "PIN_ANALOG_2") (pin "3") (pinfunction "3_3") (pintype "passive"))
    )
    (net (code "47") (name "Net-(PIN_ANALOG_1-Pad8)") (class "Default")
      (node (ref "PIN_ANALOG_1") (pin "8") (pinfunction "8_8") (pintype "passive"))
      (node (ref "PIN_ANALOG_2") (pin "7") (pinfunction "7_7") (pintype "passive"))
    )
    (net (code "48") (name "Net-(PIN_ANALOG_1-Pad10)") (class "Default")
      (node (ref "PIN_ANALOG_1") (pin "10") (pinfunction "10_10") (pintype "passive"))
      (node (ref "PIN_ANALOG_2") (pin "9") (pinfunction "9_9") (pintype "passive"))
    )
    (net (code "49") (name "Net-(PIN_ANALOG_1-Pad12)") (class "Default")
      (node (ref "PIN_ANALOG_1") (pin "12") (pinfunction "12_12") (pintype "passive"))
      (node (ref "PIN_ANALOG_2") (pin "11") (pinfunction "11_11") (pintype "passive"))
    )
    (net (code "50") (name "Net-(PIN_ANALOG_1-Pad14)") (class "Default")
      (node (ref "PIN_ANALOG_1") (pin "14") (pinfunction "14_14") (pintype "passive"))
      (node (ref "PIN_ANALOG_2") (pin "13") (pinfunction "13_13") (pintype "passive"))
    )
    (net (code "51") (name "Net-(PIN_ANALOG_2-Pad2)") (class "Default")
      (node (ref "PIN_ANALOG_2") (pin "2") (pinfunction "2_2") (pintype "passive"))
      (node (ref "PIN_ANALOG_3") (pin "1") (pinfunction "1_1") (pintype "passive"))
    )
    (net (code "52") (name "Net-(PIN_ANALOG_2-Pad4)") (class "Default")
      (node (ref "PIN_ANALOG_2") (pin "4") (pinfunction "4_4") (pintype "passive"))
      (node (ref "PIN_ANALOG_3") (pin "3") (pinfunction "3_3") (pintype "passive"))
    )
    (net (code "53") (name "Net-(PIN_ANALOG_2-Pad8)") (class "Default")
      (node (ref "PIN_ANALOG_2") (pin "8") (pinfunction "8_8") (pintype "passive"))
      (node (ref "PIN_ANALOG_3") (pin "7") (pinfunction "7_7") (pintype "passive"))
    )
    (net (code "54") (name "Net-(PIN_ANALOG_2-Pad10)") (class "Default")
      (node (ref "PIN_ANALOG_2") (pin "10") (pinfunction "10_10") (pintype "passive"))
      (node (ref "PIN_ANALOG_3") (pin "9") (pinfunction "9_9") (pintype "passive"))
    )
    (net (code "55") (name "Net-(PIN_ANALOG_2-Pad12)") (class "Default")
      (node (ref "PIN_ANALOG_2") (pin "12") (pinfunction "12_12") (pintype "passive"))
      (node (ref "PIN_ANALOG_3") (pin "11") (pinfunction "11_11") (pintype "passive"))
    )
    (net (code "56") (name "Net-(PIN_ANALOG_2-Pad14)") (class "Default")
      (node (ref "PIN_ANALOG_2") (pin "14") (pinfunction "14_14") (pintype "passive"))
      (node (ref "PIN_ANALOG_3") (pin "13") (pinfunction "13_13") (pintype "passive"))
    )
    (net (code "57") (name "Net-(PIN_ANALOG_3-Pad2)") (class "Default")
      (node (ref "PIN_ANALOG_3") (pin "2") (pinfunction "2_2") (pintype "passive"))
      (node (ref "PIN_ANALOG_4") (pin "1") (pinfunction "1_1") (pintype "passive"))
    )
    (net (code "58") (name "Net-(PIN_ANALOG_3-Pad4)") (class "Default")
      (node (ref "PIN_ANALOG_3") (pin "4") (pinfunction "4_4") (pintype "passive"))
      (node (ref "PIN_ANALOG_4") (pin "3") (pinfunction "3_3") (pintype "passive"))
    )
    (net (code "59") (name "Net-(PIN_ANALOG_3-Pad8)") (class "Default")
      (node (ref "PIN_ANALOG_3") (pin "8") (pinfunction "8_8") (pintype "passive"))
      (node (ref "PIN_ANALOG_4") (pin "7") (pinfunction "7_7") (pintype "passive"))
    )
    (net (code "60") (name "Net-(PIN_ANALOG_3-Pad10)") (class "Default")
      (node (ref "PIN_ANALOG_3") (pin "10") (pinfunction "10_10") (pintype "passive"))
      (node (ref "PIN_ANALOG_4") (pin "9") (pinfunction "9_9") (pintype "passive"))
    )
    (net (code "61") (name "Net-(PIN_ANALOG_3-Pad12)") (class "Default")
      (node (ref "PIN_ANALOG_3") (pin "12") (pinfunction "12_12") (pintype "passive"))
      (node (ref "PIN_ANALOG_4") (pin "11") (pinfunction "11_11") (pintype "passive"))
    )
    (net (code "62") (name "Net-(PIN_ANALOG_3-Pad14)") (class "Default")
      (node (ref "PIN_ANALOG_3") (pin "14") (pinfunction "14_14") (pintype "passive"))
      (node (ref "PIN_ANALOG_4") (pin "13") (pinfunction "13_13") (pintype "passive"))
    )
    (net (code "63") (name "Net-(PIN_ANALOG_4-Pad2)") (class "Default")
      (node (ref "PIN_ANALOG_4") (pin "2") (pinfunction "2_2") (pintype "passive"))
      (node (ref "PIN_ANALOG_5") (pin "1") (pinfunction "1_1") (pintype "passive"))
    )
    (net (code "64") (name "Net-(PIN_ANALOG_4-Pad4)") (class "Default")
      (node (ref "PIN_ANALOG_4") (pin "4") (pinfunction "4_4") (pintype "passive"))
      (node (ref "PIN_ANALOG_5") (pin "3") (pinfunction "3_3") (pintype "passive"))
    )
    (net (code "65") (name "Net-(PIN_ANALOG_4-Pad8)") (class "Default")
      (node (ref "PIN_ANALOG_4") (pin "8") (pinfunction "8_8") (pintype "passive"))
      (node (ref "PIN_ANALOG_5") (pin "7") (pinfunction "7_7") (pintype "passive"))
    )
    (net (code "66") (name "Net-(PIN_ANALOG_4-Pad10)") (class "Default")
      (node (ref "PIN_ANALOG_4") (pin "10") (pinfunction "10_10") (pintype "passive"))
      (node (ref "PIN_ANALOG_5") (pin "9") (pinfunction "9_9") (pintype "passive"))
    )
    (net (code "67") (name "Net-(PIN_ANALOG_4-Pad12)") (class "Default")
      (node (ref "PIN_ANALOG_4") (pin "12") (pinfunction "12_12") (pintype "passive"))
      (node (ref "PIN_ANALOG_5") (pin "11") (pinfunction "11_11") (pintype "passive"))
    )
    (net (code "68") (name "Net-(PIN_ANALOG_4-Pad14)") (class "Default")
      (node (ref "PIN_ANALOG_4") (pin "14") (pinfunction "14_14") (pintype "passive"))
      (node (ref "PIN_ANALOG_5") (pin "13") (pinfunction "13_13") (pintype "passive"))
    )
    (net (code "69") (name "Net-(PIN_ANALOG_5-Pad2)") (class "Default")
      (node (ref "PIN_ANALOG_5") (pin "2") (pinfunction "2_2") (pintype "passive"))
      (node (ref "PIN_ANALOG_6") (pin "1") (pinfunction "1_1") (pintype "passive"))
    )
    (net (code "70") (name "Net-(PIN_ANALOG_5-Pad4)") (class "Default")
      (node (ref "PIN_ANALOG_5") (pin "4") (pinfunction "4_4") (pintype "passive"))
      (node (ref "PIN_ANALOG_6") (pin "3") (pinfunction "3_3") (pintype "passive"))
    )
    (net (code "71") (name "Net-(PIN_ANALOG_5-Pad8)") (class "Default")
      (node (ref "PIN_ANALOG_5") (pin "8") (pinfunction "8_8") (pintype "passive"))
      (node (ref "PIN_ANALOG_6") (pin "7") (pinfunction "7_7") (pintype "passive"))
    )
    (net (code "72") (name "Net-(PIN_ANALOG_5-Pad10)") (class "Default")
      (node (ref "PIN_ANALOG_5") (pin "10") (pinfunction "10_10") (pintype "passive"))
      (node (ref "PIN_ANALOG_6") (pin "9") (pinfunction "9_9") (pintype "passive"))
    )
    (net (code "73") (name "Net-(PIN_ANALOG_5-Pad12)") (class "Default")
      (node (ref "PIN_ANALOG_5") (pin "12") (pinfunction "12_12") (pintype "passive"))
      (node (ref "PIN_ANALOG_6") (pin "11") (pinfunction "11_11") (pintype "passive"))
    )
    (net (code "74") (name "Net-(PIN_ANALOG_5-Pad14)") (class "Default")
      (node (ref "PIN_ANALOG_5") (pin "14") (pinfunction "14_14") (pintype "passive"))
      (node (ref "PIN_ANALOG_6") (pin "13") (pinfunction "13_13") (pintype "passive"))
    )
    (net (code "75") (name "Net-(PIN_ANALOG_6-Pad2)") (class "Default")
      (node (ref "PIN_ANALOG_6") (pin "2") (pinfunction "2_2") (pintype "passive"))
      (node (ref "PIN_ANALOG_7") (pin "1") (pinfunction "1_1") (pintype "passive"))
    )
    (net (code "76") (name "Net-(PIN_ANALOG_6-Pad4)") (class "Default")
      (node (ref "PIN_ANALOG_6") (pin "4") (pinfunction "4_4") (pintype "passive"))
      (node (ref "PIN_ANALOG_7") (pin "3") (pinfunction "3_3") (pintype "passive"))
    )
    (net (code "77") (name "Net-(PIN_ANALOG_6-Pad8)") (class "Default")
      (node (ref "PIN_ANALOG_6") (pin "8") (pinfunction "8_8") (pintype "passive"))
      (node (ref "PIN_ANALOG_7") (pin "7") (pinfunction "7_7") (pintype "passive"))
    )
    (net (code "78") (name "Net-(PIN_ANALOG_6-Pad10)") (class "Default")
      (node (ref "PIN_ANALOG_6") (pin "10") (pinfunction "10_10") (pintype "passive"))
      (node (ref "PIN_ANALOG_7") (pin "9") (pinfunction "9_9") (pintype "passive"))
    )
    (net (code "79") (name "Net-(PIN_ANALOG_6-Pad12)") (class "Default")
      (node (ref "PIN_ANALOG_6") (pin "12") (pinfunction "12_12") (pintype "passive"))
      (node (ref "PIN_ANALOG_7") (pin "11") (pinfunction "11_11") (pintype "passive"))
    )
    (net (code "80") (name "Net-(PIN_ANALOG_6-Pad14)") (class "Default")
      (node (ref "PIN_ANALOG_6") (pin "14") (pinfunction "14_14") (pintype "passive"))
      (node (ref "PIN_ANALOG_7") (pin "13") (pinfunction "13_13") (pintype "passive"))
    )
    (net (code "81") (name "Net-(PIN_ANALOG_7-Pad2)") (class "Default")
      (node (ref "PIN_ANALOG_7") (pin "2") (pinfunction "2_2") (pintype "passive"))
      (node (ref "PIN_ANALOG_8") (pin "1") (pinfunction "1_1") (pintype "passive"))
    )
    (net (code "82") (name "Net-(PIN_ANALOG_7-Pad4)") (class "Default")
      (node (ref "PIN_ANALOG_7") (pin "4") (pinfunction "4_4") (pintype "passive"))
      (node (ref "PIN_ANALOG_8") (pin "3") (pinfunction "3_3") (pintype "passive"))
    )
    (net (code "83") (name "Net-(PIN_ANALOG_7-Pad8)") (class "Default")
      (node (ref "PIN_ANALOG_7") (pin "8") (pinfunction "8_8") (pintype "passive"))
      (node (ref "PIN_ANALOG_8") (pin "7") (pinfunction "7_7") (pintype "passive"))
    )
    (net (code "84") (name "Net-(PIN_ANALOG_7-Pad10)") (class "Default")
      (node (ref "PIN_ANALOG_7") (pin "10") (pinfunction "10_10") (pintype "passive"))
      (node (ref "PIN_ANALOG_8") (pin "9") (pinfunction "9_9") (pintype "passive"))
    )
    (net (code "85") (name "Net-(PIN_ANALOG_7-Pad12)") (class "Default")
      (node (ref "PIN_ANALOG_7") (pin "12") (pinfunction "12_12") (pintype "passive"))
      (node (ref "PIN_ANALOG_8") (pin "11") (pinfunction "11_11") (pintype "passive"))
    )
    (net (code "86") (name "Net-(PIN_ANALOG_7-Pad14)") (class "Default")
      (node (ref "PIN_ANALOG_7") (pin "14") (pinfunction "14_14") (pintype "passive"))
      (node (ref "PIN_ANALOG_8") (pin "13") (pinfunction "13_13") (pintype "passive"))
    )
    (net (code "87") (name "Net-(PIN_ANALOG_8-Pad2)") (class "Default")
      (node (ref "PIN_ANALOG_8") (pin "2") (pinfunction "2_2") (pintype "passive"))
      (node (ref "PIN_ANALOG_9") (pin "1") (pinfunction "1_1") (pintype "passive"))
    )
    (net (code "88") (name "Net-(PIN_ANALOG_8-Pad4)") (class "Default")
      (node (ref "PIN_ANALOG_8") (pin "4") (pinfunction "4_4") (pintype "passive"))
      (node (ref "PIN_ANALOG_9") (pin "3") (pinfunction "3_3") (pintype "passive"))
    )
    (net (code "89") (name "Net-(PIN_ANALOG_8-Pad8)") (class "Default")
      (node (ref "PIN_ANALOG_8") (pin "8") (pinfunction "8_8") (pintype "passive"))
      (node (ref "PIN_ANALOG_9") (pin "7") (pinfunction "7_7") (pintype "passive"))
    )
    (net (code "90") (name "Net-(PIN_ANALOG_8-Pad10)") (class "Default")
      (node (ref "PIN_ANALOG_8") (pin "10") (pinfunction "10_10") (pintype "passive"))
      (node (ref "PIN_ANALOG_9") (pin "9") (pinfunction "9_9") (pintype "passive"))
    )
    (net (code "91") (name "Net-(PIN_ANALOG_8-Pad12)") (class "Default")
      (node (ref "PIN_ANALOG_8") (pin "12") (pinfunction "12_12") (pintype "passive"))
      (node (ref "PIN_ANALOG_9") (pin "11") (pinfunction "11_11") (pintype "passive"))
    )
    (net (code "92") (name "Net-(PIN_ANALOG_8-Pad14)") (class "Default")
      (node (ref "PIN_ANALOG_8") (pin "14") (pinfunction "14_14") (pintype "passive"))
      (node (ref "PIN_ANALOG_9") (pin "13") (pinfunction "13_13") (pintype "passive"))
    )
    (net (code "93") (name "Net-(PIN_ANALOG_10-Pad1)") (class "Default")
      (node (ref "PIN_ANALOG_10") (pin "1") (pinfunction "1_1") (pintype "passive"))
      (node (ref "PIN_ANALOG_9") (pin "2") (pinfunction "2_2") (pintype "passive"))
    )
    (net (code "94") (name "Net-(PIN_ANALOG_10-Pad2)") (class "Default")
      (node (ref "PIN_ANALOG_10") (pin "2") (pinfunction "2_2") (pintype "passive"))
      (node (ref "PIN_ANALOG_11") (pin "1") (pinfunction "1_1") (pintype "passive"))
    )
    (net (code "95") (name "Net-(PIN_ANALOG_10-Pad3)") (class "Default")
      (node (ref "PIN_ANALOG_10") (pin "3") (pinfunction "3_3") (pintype "passive"))
      (node (ref "PIN_ANALOG_9") (pin "4") (pinfunction "4_4") (pintype "passive"))
    )
    (net (code "96") (name "Net-(PIN_ANALOG_10-Pad4)") (class "Default")
      (node (ref "PIN_ANALOG_10") (pin "4") (pinfunction "4_4") (pintype "passive"))
      (node (ref "PIN_ANALOG_11") (pin "3") (pinfunction "3_3") (pintype "passive"))
    )
    (net (code "97") (name "Net-(PIN_ANALOG_10-Pad7)") (class "Default")
      (node (ref "PIN_ANALOG_10") (pin "7") (pinfunction "7_7") (pintype "passive"))
      (node (ref "PIN_ANALOG_9") (pin "8") (pinfunction "8_8") (pintype "passive"))
    )
    (net (code "98") (name "Net-(PIN_ANALOG_10-Pad8)") (class "Default")
      (node (ref "PIN_ANALOG_10") (pin "8") (pinfunction "8_8") (pintype "passive"))
      (node (ref "PIN_ANALOG_11") (pin "7") (pinfunction "7_7") (pintype "passive"))
    )
    (net (code "99") (name "Net-(PIN_ANALOG_10-Pad9)") (class "Default")
      (node (ref "PIN_ANALOG_10") (pin "9") (pinfunction "9_9") (pintype "passive"))
      (node (ref "PIN_ANALOG_9") (pin "10") (pinfunction "10_10") (pintype "passive"))
    )
    (net (code "100") (name "Net-(PIN_ANALOG_10-Pad10)") (class "Default")
      (node (ref "PIN_ANALOG_10") (pin "10") (pinfunction "10_10") (pintype "passive"))
      (node (ref "PIN_ANALOG_11") (pin "9") (pinfunction "9_9") (pintype "passive"))
    )
    (net (code "101") (name "Net-(PIN_ANALOG_10-Pad11)") (class "Default")
      (node (ref "PIN_ANALOG_10") (pin "11") (pinfunction "11_11") (pintype "passive"))
      (node (ref "PIN_ANALOG_9") (pin "12") (pinfunction "12_12") (pintype "passive"))
    )
    (net (code "102") (name "Net-(PIN_ANALOG_10-Pad12)") (class "Default")
      (node (ref "PIN_ANALOG_10") (pin "12") (pinfunction "12_12") (pintype "passive"))
      (node (ref "PIN_ANALOG_11") (pin "11") (pinfunction "11_11") (pintype "passive"))
    )
    (net (code "103") (name "Net-(PIN_ANALOG_10-Pad13)") (class "Default")
      (node (ref "PIN_ANALOG_10") (pin "13") (pinfunction "13_13") (pintype "passive"))
      (node (ref "PIN_ANALOG_9") (pin "14") (pinfunction "14_14") (pintype "passive"))
    )
    (net (code "104") (name "Net-(PIN_ANALOG_10-Pad14)") (class "Default")
      (node (ref "PIN_ANALOG_10") (pin "14") (pinfunction "14_14") (pintype "passive"))
      (node (ref "PIN_ANALOG_11") (pin "13") (pinfunction "13_13") (pintype "passive"))
    )
    (net (code "105") (name "Net-(PIN_ANALOG_11-Pad2)") (class "Default")
      (node (ref "PIN_ANALOG_11") (pin "2") (pinfunction "2_2") (pintype "passive"))
      (node (ref "PIN_ANALOG_12") (pin "1") (pinfunction "1_1") (pintype "passive"))
    )
    (net (code "106") (name "Net-(PIN_ANALOG_11-Pad4)") (class "Default")
      (node (ref "PIN_ANALOG_11") (pin "4") (pinfunction "4_4") (pintype "passive"))
      (node (ref "PIN_ANALOG_12") (pin "3") (pinfunction "3_3") (pintype "passive"))
    )
    (net (code "107") (name "Net-(PIN_ANALOG_11-Pad8)") (class "Default")
      (node (ref "PIN_ANALOG_11") (pin "8") (pinfunction "8_8") (pintype "passive"))
      (node (ref "PIN_ANALOG_12") (pin "7") (pinfunction "7_7") (pintype "passive"))
    )
    (net (code "108") (name "Net-(PIN_ANALOG_11-Pad10)") (class "Default")
      (node (ref "PIN_ANALOG_11") (pin "10") (pinfunction "10_10") (pintype "passive"))
      (node (ref "PIN_ANALOG_12") (pin "9") (pinfunction "9_9") (pintype "passive"))
    )
    (net (code "109") (name "Net-(PIN_ANALOG_11-Pad12)") (class "Default")
      (node (ref "PIN_ANALOG_11") (pin "12") (pinfunction "12_12") (pintype "passive"))
      (node (ref "PIN_ANALOG_12") (pin "11") (pinfunction "11_11") (pintype "passive"))
    )
    (net (code "110") (name "Net-(PIN_ANALOG_11-Pad14)") (class "Default")
      (node (ref "PIN_ANALOG_11") (pin "14") (pinfunction "14_14") (pintype "passive"))
      (node (ref "PIN_ANALOG_12") (pin "13") (pinfunction "13_13") (pintype "passive"))
    )
    (net (code "111") (name "Net-(PIN_ANALOG_12-Pad2)") (class "Default")
      (node (ref "PIN_ANALOG_12") (pin "2") (pinfunction "2_2") (pintype "passive"))
      (node (ref "PIN_ANALOG_13") (pin "1") (pinfunction "1_1") (pintype "passive"))
    )
    (net (code "112") (name "Net-(PIN_ANALOG_12-Pad4)") (class "Default")
      (node (ref "PIN_ANALOG_12") (pin "4") (pinfunction "4_4") (pintype "passive"))
      (node (ref "PIN_ANALOG_13") (pin "3") (pinfunction "3_3") (pintype "passive"))
    )
    (net (code "113") (name "Net-(PIN_ANALOG_12-Pad8)") (class "Default")
      (node (ref "PIN_ANALOG_12") (pin "8") (pinfunction "8_8") (pintype "passive"))
      (node (ref "PIN_ANALOG_13") (pin "7") (pinfunction "7_7") (pintype "passive"))
    )
    (net (code "114") (name "Net-(PIN_ANALOG_12-Pad10)") (class "Default")
      (node (ref "PIN_ANALOG_12") (pin "10") (pinfunction "10_10") (pintype "passive"))
      (node (ref "PIN_ANALOG_13") (pin "9") (pinfunction "9_9") (pintype "passive"))
    )
    (net (code "115") (name "Net-(PIN_ANALOG_12-Pad12)") (class "Default")
      (node (ref "PIN_ANALOG_12") (pin "12") (pinfunction "12_12") (pintype "passive"))
      (node (ref "PIN_ANALOG_13") (pin "11") (pinfunction "11_11") (pintype "passive"))
    )
    (net (code "116") (name "Net-(PIN_ANALOG_12-Pad14)") (class "Default")
      (node (ref "PIN_ANALOG_12") (pin "14") (pinfunction "14_14") (pintype "passive"))
      (node (ref "PIN_ANALOG_13") (pin "13") (pinfunction "13_13") (pintype "passive"))
    )
    (net (code "117") (name "Net-(PIN_ANALOG_13-Pad2)") (class "Default")
      (node (ref "PIN_ANALOG_13") (pin "2") (pinfunction "2_2") (pintype "passive"))
      (node (ref "PIN_ANALOG_14") (pin "1") (pinfunction "1_1") (pintype "passive"))
    )
    (net (code "118") (name "Net-(PIN_ANALOG_13-Pad4)") (class "Default")
      (node (ref "PIN_ANALOG_13") (pin "4") (pinfunction "4_4") (pintype "passive"))
      (node (ref "PIN_ANALOG_14") (pin "3") (pinfunction "3_3") (pintype "passive"))
    )
    (net (code "119") (name "Net-(PIN_ANALOG_13-Pad8)") (class "Default")
      (node (ref "PIN_ANALOG_13") (pin "8") (pinfunction "8_8") (pintype "passive"))
      (node (ref "PIN_ANALOG_14") (pin "7") (pinfunction "7_7") (pintype "passive"))
    )
    (net (code "120") (name "Net-(PIN_ANALOG_13-Pad10)") (class "Default")
      (node (ref "PIN_ANALOG_13") (pin "10") (pinfunction "10_10") (pintype "passive"))
      (node (ref "PIN_ANALOG_14") (pin "9") (pinfunction "9_9") (pintype "passive"))
    )
    (net (code "121") (name "Net-(PIN_ANALOG_13-Pad12)") (class "Default")
      (node (ref "PIN_ANALOG_13") (pin "12") (pinfunction "12_12") (pintype "passive"))
      (node (ref "PIN_ANALOG_14") (pin "11") (pinfunction "11_11") (pintype "passive"))
    )
    (net (code "122") (name "Net-(PIN_ANALOG_13-Pad14)") (class "Default")
      (node (ref "PIN_ANALOG_13") (pin "14") (pinfunction "14_14") (pintype "passive"))
      (node (ref "PIN_ANALOG_14") (pin "13") (pinfunction "13_13") (pintype "passive"))
    )
    (net (code "123") (name "Net-(PIN_ANALOG_14-Pad2)") (class "Default")
      (node (ref "PIN_ANALOG_14") (pin "2") (pinfunction "2_2") (pintype "passive"))
      (node (ref "PIN_ANALOG_15") (pin "1") (pinfunction "1_1") (pintype "passive"))
    )
    (net (code "124") (name "Net-(PIN_ANALOG_14-Pad4)") (class "Default")
      (node (ref "PIN_ANALOG_14") (pin "4") (pinfunction "4_4") (pintype "passive"))
      (node (ref "PIN_ANALOG_15") (pin "3") (pinfunction "3_3") (pintype "passive"))
    )
    (net (code "125") (name "Net-(PIN_ANALOG_14-Pad8)") (class "Default")
      (node (ref "PIN_ANALOG_14") (pin "8") (pinfunction "8_8") (pintype "passive"))
      (node (ref "PIN_ANALOG_15") (pin "7") (pinfunction "7_7") (pintype "passive"))
    )
    (net (code "126") (name "Net-(PIN_ANALOG_14-Pad10)") (class "Default")
      (node (ref "PIN_ANALOG_14") (pin "10") (pinfunction "10_10") (pintype "passive"))
      (node (ref "PIN_ANALOG_15") (pin "9") (pinfunction "9_9") (pintype "passive"))
    )
    (net (code "127") (name "Net-(PIN_ANALOG_14-Pad12)") (class "Default")
      (node (ref "PIN_ANALOG_14") (pin "12") (pinfunction "12_12") (pintype "passive"))
      (node (ref "PIN_ANALOG_15") (pin "11") (pinfunction "11_11") (pintype "passive"))
    )
    (net (code "128") (name "Net-(PIN_ANALOG_14-Pad14)") (class "Default")
      (node (ref "PIN_ANALOG_14") (pin "14") (pinfunction "14_14") (pintype "passive"))
      (node (ref "PIN_ANALOG_15") (pin "13") (pinfunction "13_13") (pintype "passive"))
    )
    (net (code "129") (name "Net-(PIN_ANALOG_15-Pad2)") (class "Default")
      (node (ref "PIN_ANALOG_15") (pin "2") (pinfunction "2_2") (pintype "passive"))
      (node (ref "PIN_ANALOG_16") (pin "1") (pinfunction "1_1") (pintype "passive"))
    )
    (net (code "130") (name "Net-(PIN_ANALOG_15-Pad4)") (class "Default")
      (node (ref "PIN_ANALOG_15") (pin "4") (pinfunction "4_4") (pintype "passive"))
      (node (ref "PIN_ANALOG_16") (pin "3") (pinfunction "3_3") (pintype "passive"))
    )
    (net (code "131") (name "Net-(PIN_ANALOG_15-Pad8)") (class "Default")
      (node (ref "PIN_ANALOG_15") (pin "8") (pinfunction "8_8") (pintype "passive"))
      (node (ref "PIN_ANALOG_16") (pin "7") (pinfunction "7_7") (pintype "passive"))
    )
    (net (code "132") (name "Net-(PIN_ANALOG_15-Pad10)") (class "Default")
      (node (ref "PIN_ANALOG_15") (pin "10") (pinfunction "10_10") (pintype "passive"))
      (node (ref "PIN_ANALOG_16") (pin "9") (pinfunction "9_9") (pintype "passive"))
    )
    (net (code "133") (name "Net-(PIN_ANALOG_15-Pad12)") (class "Default")
      (node (ref "PIN_ANALOG_15") (pin "12") (pinfunction "12_12") (pintype "passive"))
      (node (ref "PIN_ANALOG_16") (pin "11") (pinfunction "11_11") (pintype "passive"))
    )
    (net (code "134") (name "Net-(PIN_ANALOG_15-Pad14)") (class "Default")
      (node (ref "PIN_ANALOG_15") (pin "14") (pinfunction "14_14") (pintype "passive"))
      (node (ref "PIN_ANALOG_16") (pin "13") (pinfunction "13_13") (pintype "passive"))
    )
    (net (code "135") (name "Net-(PIN_ANALOG_16-Pad2)") (class "Default")
      (node (ref "PIN_ANALOG_16") (pin "2") (pinfunction "2_2") (pintype "passive"))
      (node (ref "PIN_ANALOG_17") (pin "1") (pinfunction "1_1") (pintype "passive"))
    )
    (net (code "136") (name "Net-(PIN_ANALOG_16-Pad4)") (class "Default")
      (node (ref "PIN_ANALOG_16") (pin "4") (pinfunction "4_4") (pintype "passive"))
      (node (ref "PIN_ANALOG_17") (pin "3") (pinfunction "3_3") (pintype "passive"))
    )
    (net (code "137") (name "Net-(PIN_ANALOG_16-Pad8)") (class "Default")
      (node (ref "PIN_ANALOG_16") (pin "8") (pinfunction "8_8") (pintype "passive"))
      (node (ref "PIN_ANALOG_17") (pin "7") (pinfunction "7_7") (pintype "passive"))
    )
    (net (code "138") (name "Net-(PIN_ANALOG_16-Pad10)") (class "Default")
      (node (ref "PIN_ANALOG_16") (pin "10") (pinfunction "10_10") (pintype "passive"))
      (node (ref "PIN_ANALOG_17") (pin "9") (pinfunction "9_9") (pintype "passive"))
    )
    (net (code "139") (name "Net-(PIN_ANALOG_16-Pad12)") (class "Default")
      (node (ref "PIN_ANALOG_16") (pin "12") (pinfunction "12_12") (pintype "passive"))
      (node (ref "PIN_ANALOG_17") (pin "11") (pinfunction "11_11") (pintype "passive"))
    )
    (net (code "140") (name "Net-(PIN_ANALOG_16-Pad14)") (class "Default")
      (node (ref "PIN_ANALOG_16") (pin "14") (pinfunction "14_14") (pintype "passive"))
      (node (ref "PIN_ANALOG_17") (pin "13") (pinfunction "13_13") (pintype "passive"))
    )
    (net (code "141") (name "Net-(PIN_ANALOG_17-Pad2)") (class "Default")
      (node (ref "PIN_ANALOG_17") (pin "2") (pinfunction "2_2") (pintype "passive"))
      (node (ref "PIN_ANALOG_18") (pin "1") (pinfunction "1_1") (pintype "passive"))
    )
    (net (code "142") (name "Net-(PIN_ANALOG_17-Pad4)") (class "Default")
      (node (ref "PIN_ANALOG_17") (pin "4") (pinfunction "4_4") (pintype "passive"))
      (node (ref "PIN_ANALOG_18") (pin "3") (pinfunction "3_3") (pintype "passive"))
    )
    (net (code "143") (name "Net-(PIN_ANALOG_17-Pad8)") (class "Default")
      (node (ref "PIN_ANALOG_17") (pin "8") (pinfunction "8_8") (pintype "passive"))
      (node (ref "PIN_ANALOG_18") (pin "7") (pinfunction "7_7") (pintype "passive"))
    )
    (net (code "144") (name "Net-(PIN_ANALOG_17-Pad10)") (class "Default")
      (node (ref "PIN_ANALOG_17") (pin "10") (pinfunction "10_10") (pintype "passive"))
      (node (ref "PIN_ANALOG_18") (pin "9") (pinfunction "9_9") (pintype "passive"))
    )
    (net (code "145") (name "Net-(PIN_ANALOG_17-Pad12)") (class "Default")
      (node (ref "PIN_ANALOG_17") (pin "12") (pinfunction "12_12") (pintype "passive"))
      (node (ref "PIN_ANALOG_18") (pin "11") (pinfunction "11_11") (pintype "passive"))
    )
    (net (code "146") (name "Net-(PIN_ANALOG_17-Pad14)") (class "Default")
      (node (ref "PIN_ANALOG_17") (pin "14") (pinfunction "14_14") (pintype "passive"))
      (node (ref "PIN_ANALOG_18") (pin "13") (pinfunction "13_13") (pintype "passive"))
    )
    (net (code "147") (name "Net-(PIN_ANALOG_18-Pad2)") (class "Default")
      (node (ref "PIN_ANALOG_18") (pin "2") (pinfunction "2_2") (pintype "passive"))
      (node (ref "PIN_ANALOG_19") (pin "1") (pinfunction "1_1") (pintype "passive"))
    )
    (net (code "148") (name "Net-(PIN_ANALOG_18-Pad4)") (class "Default")
      (node (ref "PIN_ANALOG_18") (pin "4") (pinfunction "4_4") (pintype "passive"))
      (node (ref "PIN_ANALOG_19") (pin "3") (pinfunction "3_3") (pintype "passive"))
    )
    (net (code "149") (name "Net-(PIN_ANALOG_18-Pad8)") (class "Default")
      (node (ref "PIN_ANALOG_18") (pin "8") (pinfunction "8_8") (pintype "passive"))
      (node (ref "PIN_ANALOG_19") (pin "7") (pinfunction "7_7") (pintype "passive"))
    )
    (net (code "150") (name "Net-(PIN_ANALOG_18-Pad10)") (class "Default")
      (node (ref "PIN_ANALOG_18") (pin "10") (pinfunction "10_10") (pintype "passive"))
      (node (ref "PIN_ANALOG_19") (pin "9") (pinfunction "9_9") (pintype "passive"))
    )
    (net (code "151") (name "Net-(PIN_ANALOG_18-Pad12)") (class "Default")
      (node (ref "PIN_ANALOG_18") (pin "12") (pinfunction "12_12") (pintype "passive"))
      (node (ref "PIN_ANALOG_19") (pin "11") (pinfunction "11_11") (pintype "passive"))
    )
    (net (code "152") (name "Net-(PIN_ANALOG_18-Pad14)") (class "Default")
      (node (ref "PIN_ANALOG_18") (pin "14") (pinfunction "14_14") (pintype "passive"))
      (node (ref "PIN_ANALOG_19") (pin "13") (pinfunction "13_13") (pintype "passive"))
    )
    (net (code "153") (name "Net-(PIN_ANALOG_19-Pad2)") (class "Default")
      (node (ref "PIN_ANALOG_19") (pin "2") (pinfunction "2_2") (pintype "passive"))
      (node (ref "PIN_ANALOG_20") (pin "1") (pinfunction "1_1") (pintype "passive"))
    )
    (net (code "154") (name "Net-(PIN_ANALOG_19-Pad4)") (class "Default")
      (node (ref "PIN_ANALOG_19") (pin "4") (pinfunction "4_4") (pintype "passive"))
      (node (ref "PIN_ANALOG_20") (pin "3") (pinfunction "3_3") (pintype "passive"))
    )
    (net (code "155") (name "Net-(PIN_ANALOG_19-Pad8)") (class "Default")
      (node (ref "PIN_ANALOG_19") (pin "8") (pinfunction "8_8") (pintype "passive"))
      (node (ref "PIN_ANALOG_20") (pin "7") (pinfunction "7_7") (pintype "passive"))
    )
    (net (code "156") (name "Net-(PIN_ANALOG_19-Pad10)") (class "Default")
      (node (ref "PIN_ANALOG_19") (pin "10") (pinfunction "10_10") (pintype "passive"))
      (node (ref "PIN_ANALOG_20") (pin "9") (pinfunction "9_9") (pintype "passive"))
    )
    (net (code "157") (name "Net-(PIN_ANALOG_19-Pad12)") (class "Default")
      (node (ref "PIN_ANALOG_19") (pin "12") (pinfunction "12_12") (pintype "passive"))
      (node (ref "PIN_ANALOG_20") (pin "11") (pinfunction "11_11") (pintype "passive"))
    )
    (net (code "158") (name "Net-(PIN_ANALOG_19-Pad14)") (class "Default")
      (node (ref "PIN_ANALOG_19") (pin "14") (pinfunction "14_14") (pintype "passive"))
      (node (ref "PIN_ANALOG_20") (pin "13") (pinfunction "13_13") (pintype "passive"))
    )
    (net (code "159") (name "Net-(PIN_ANALOG_20-Pad2)") (class "Default")
      (node (ref "PIN_ANALOG_20") (pin "2") (pinfunction "2_2") (pintype "passive"))
      (node (ref "PIN_ANALOG_21") (pin "1") (pinfunction "1_1") (pintype "passive"))
    )
    (net (code "160") (name "Net-(PIN_ANALOG_20-Pad4)") (class "Default")
      (node (ref "PIN_ANALOG_20") (pin "4") (pinfunction "4_4") (pintype "passive"))
      (node (ref "PIN_ANALOG_21") (pin "3") (pinfunction "3_3") (pintype "passive"))
    )
    (net (code "161") (name "Net-(PIN_ANALOG_20-Pad8)") (class "Default")
      (node (ref "PIN_ANALOG_20") (pin "8") (pinfunction "8_8") (pintype "passive"))
      (node (ref "PIN_ANALOG_21") (pin "7") (pinfunction "7_7") (pintype "passive"))
    )
    (net (code "162") (name "Net-(PIN_ANALOG_20-Pad10)") (class "Default")
      (node (ref "PIN_ANALOG_20") (pin "10") (pinfunction "10_10") (pintype "passive"))
      (node (ref "PIN_ANALOG_21") (pin "9") (pinfunction "9_9") (pintype "passive"))
    )
    (net (code "163") (name "Net-(PIN_ANALOG_20-Pad12)") (class "Default")
      (node (ref "PIN_ANALOG_20") (pin "12") (pinfunction "12_12") (pintype "passive"))
      (node (ref "PIN_ANALOG_21") (pin "11") (pinfunction "11_11") (pintype "passive"))
    )
    (net (code "164") (name "Net-(PIN_ANALOG_20-Pad14)") (class "Default")
      (node (ref "PIN_ANALOG_20") (pin "14") (pinfunction "14_14") (pintype "passive"))
      (node (ref "PIN_ANALOG_21") (pin "13") (pinfunction "13_13") (pintype "passive"))
    )
    (net (code "165") (name "unconnected-(PIN_AIN_PWRGND3-Pad2)") (class "Default")
      (node (ref "PIN_AIN_PWRGND3") (pin "2") (pinfunction "2_2") (pintype "passive"))
    )
    (net (code "166") (name "unconnected-(PIN_AIN_PWRGND3-Pad3)") (class "Default")
      (node (ref "PIN_AIN_PWRGND3") (pin "3") (pinfunction "3_3") (pintype "passive"))
    )
    (net (code "167") (name "unconnected-(PIN_AIN_PWRGND3-Pad4)") (class "Default")
      (node (ref "PIN_AIN_PWRGND3") (pin "4") (pinfunction "4_4") (pintype "passive"))
    )
    (net (code "168") (name "unconnected-(PIN_AIN_PWRGND3-Pad5)") (class "Default")
      (node (ref "PIN_AIN_PWRGND3") (pin "5") (pinfunction "5_5") (pintype "passive"))
    )
    (net (code "169") (name "unconnected-(PIN_AIN_PWRGND3-Pad7)") (class "Default")
      (node (ref "PIN_AIN_PWRGND3") (pin "7") (pinfunction "7_7") (pintype "passive"))
    )
    (net (code "170") (name "unconnected-(PIN_AIN_PWRGND3-Pad9)") (class "Default")
      (node (ref "PIN_AIN_PWRGND3") (pin "9") (pinfunction "9_9") (pintype "passive"))
    )
    (net (code "171") (name "unconnected-(PIN_AIN_PWRGND3-Pad11)") (class "Default")
      (node (ref "PIN_AIN_PWRGND3") (pin "11") (pinfunction "11_11") (pintype "passive"))
    )
    (net (code "172") (name "unconnected-(PIN_AIN_PWRGND3-Pad13)") (class "Default")
      (node (ref "PIN_AIN_PWRGND3") (pin "13") (pinfunction "13_13") (pintype "passive"))
    )
    (net (code "173") (name "unconnected-(PIN_AIN_PWRGND4-Pad2)") (class "Default")
      (node (ref "PIN_AIN_PWRGND4") (pin "2") (pinfunction "2_2") (pintype "passive"))
    )
    (net (code "174") (name "unconnected-(PIN_AIN_PWRGND4-Pad3)") (class "Default")
      (node (ref "PIN_AIN_PWRGND4") (pin "3") (pinfunction "3_3") (pintype "passive"))
    )
    (net (code "175") (name "unconnected-(PIN_AIN_PWRGND4-Pad4)") (class "Default")
      (node (ref "PIN_AIN_PWRGND4") (pin "4") (pinfunction "4_4") (pintype "passive"))
    )
    (net (code "176") (name "unconnected-(PIN_AIN_PWRGND4-Pad5)") (class "Default")
      (node (ref "PIN_AIN_PWRGND4") (pin "5") (pinfunction "5_5") (pintype "passive"))
    )
    (net (code "177") (name "unconnected-(PIN_AIN_PWRGND4-Pad7)") (class "Default")
      (node (ref "PIN_AIN_PWRGND4") (pin "7") (pinfunction "7_7") (pintype "passive"))
    )
    (net (code "178") (name "unconnected-(PIN_AIN_PWRGND4-Pad9)") (class "Default")
      (node (ref "PIN_AIN_PWRGND4") (pin "9") (pinfunction "9_9") (pintype "passive"))
    )
    (net (code "179") (name "unconnected-(PIN_AIN_PWRGND4-Pad11)") (class "Default")
      (node (ref "PIN_AIN_PWRGND4") (pin "11") (pinfunction "11_11") (pintype "passive"))
    )
    (net (code "180") (name "unconnected-(PIN_AIN_PWRGND4-Pad13)") (class "Default")
      (node (ref "PIN_AIN_PWRGND4") (pin "13") (pinfunction "13_13") (pintype "passive"))
    )
    (net (code "181") (name "unconnected-(PIN_AIN_PWRGND5-Pad2)") (class "Default")
      (node (ref "PIN_AIN_PWRGND5") (pin "2") (pinfunction "2_2") (pintype "passive"))
    )
    (net (code "182") (name "unconnected-(PIN_AIN_PWRGND5-Pad3)") (class "Default")
      (node (ref "PIN_AIN_PWRGND5") (pin "3") (pinfunction "3_3") (pintype "passive"))
    )
    (net (code "183") (name "unconnected-(PIN_AIN_PWRGND5-Pad4)") (class "Default")
      (node (ref "PIN_AIN_PWRGND5") (pin "4") (pinfunction "4_4") (pintype "passive"))
    )
    (net (code "184") (name "unconnected-(PIN_AIN_PWRGND5-Pad5)") (class "Default")
      (node (ref "PIN_AIN_PWRGND5") (pin "5") (pinfunction "5_5") (pintype "passive"))
    )
    (net (code "185") (name "unconnected-(PIN_AIN_PWRGND5-Pad7)") (class "Default")
      (node (ref "PIN_AIN_PWRGND5") (pin "7") (pinfunction "7_7") (pintype "passive"))
    )
    (net (code "186") (name "unconnected-(PIN_AIN_PWRGND5-Pad9)") (class "Default")
      (node (ref "PIN_AIN_PWRGND5") (pin "9") (pinfunction "9_9") (pintype "passive"))
    )
    (net (code "187") (name "unconnected-(PIN_AIN_PWRGND5-Pad11)") (class "Default")
      (node (ref "PIN_AIN_PWRGND5") (pin "11") (pinfunction "11_11") (pintype "passive"))
    )
    (net (code "188") (name "unconnected-(PIN_AIN_PWRGND5-Pad13)") (class "Default")
      (node (ref "PIN_AIN_PWRGND5") (pin "13") (pinfunction "13_13") (pintype "passive"))
    )
    (net (code "189") (name "unconnected-(PIN_AIN_PWRGND6-Pad2)") (class "Default")
      (node (ref "PIN_AIN_PWRGND6") (pin "2") (pinfunction "2_2") (pintype "passive"))
    )
    (net (code "190") (name "unconnected-(PIN_AIN_PWRGND6-Pad3)") (class "Default")
      (node (ref "PIN_AIN_PWRGND6") (pin "3") (pinfunction "3_3") (pintype "passive"))
    )
    (net (code "191") (name "unconnected-(PIN_AIN_PWRGND6-Pad4)") (class "Default")
      (node (ref "PIN_AIN_PWRGND6") (pin "4") (pinfunction "4_4") (pintype "passive"))
    )
    (net (code "192") (name "unconnected-(PIN_AIN_PWRGND6-Pad5)") (class "Default")
      (node (ref "PIN_AIN_PWRGND6") (pin "5") (pinfunction "5_5") (pintype "passive"))
    )
    (net (code "193") (name "unconnected-(PIN_AIN_PWRGND6-Pad7)") (class "Default")
      (node (ref "PIN_AIN_PWRGND6") (pin "7") (pinfunction "7_7") (pintype "passive"))
    )
    (net (code "194") (name "unconnected-(PIN_AIN_PWRGND6-Pad9)") (class "Default")
      (node (ref "PIN_AIN_PWRGND6") (pin "9") (pinfunction "9_9") (pintype "passive"))
    )
    (net (code "195") (name "unconnected-(PIN_AIN_PWRGND6-Pad11)") (class "Default")
      (node (ref "PIN_AIN_PWRGND6") (pin "11") (pinfunction "11_11") (pintype "passive"))
    )
    (net (code "196") (name "unconnected-(PIN_AIN_PWRGND6-Pad13)") (class "Default")
      (node (ref "PIN_AIN_PWRGND6") (pin "13") (pinfunction "13_13") (pintype "passive"))
    )
    (net (code "197") (name "unconnected-(PIN_AIN_PWRGND7-Pad2)") (class "Default")
      (node (ref "PIN_AIN_PWRGND7") (pin "2") (pinfunction "2_2") (pintype "passive"))
    )
    (net (code "198") (name "unconnected-(PIN_AIN_PWRGND7-Pad3)") (class "Default")
      (node (ref "PIN_AIN_PWRGND7") (pin "3") (pinfunction "3_3") (pintype "passive"))
    )
    (net (code "199") (name "unconnected-(PIN_AIN_PWRGND7-Pad4)") (class "Default")
      (node (ref "PIN_AIN_PWRGND7") (pin "4") (pinfunction "4_4") (pintype "passive"))
    )
    (net (code "200") (name "unconnected-(PIN_AIN_PWRGND7-Pad5)") (class "Default")
      (node (ref "PIN_AIN_PWRGND7") (pin "5") (pinfunction "5_5") (pintype "passive"))
    )
    (net (code "201") (name "unconnected-(PIN_AIN_PWRGND7-Pad7)") (class "Default")
      (node (ref "PIN_AIN_PWRGND7") (pin "7") (pinfunction "7_7") (pintype "passive"))
    )
    (net (code "202") (name "unconnected-(PIN_AIN_PWRGND7-Pad9)") (class "Default")
      (node (ref "PIN_AIN_PWRGND7") (pin "9") (pinfunction "9_9") (pintype "passive"))
    )
    (net (code "203") (name "unconnected-(PIN_AIN_PWRGND7-Pad11)") (class "Default")
      (node (ref "PIN_AIN_PWRGND7") (pin "11") (pinfunction "11_11") (pintype "passive"))
    )
    (net (code "204") (name "unconnected-(PIN_AIN_PWRGND7-Pad13)") (class "Default")
      (node (ref "PIN_AIN_PWRGND7") (pin "13") (pinfunction "13_13") (pintype "passive"))
    )
    (net (code "205") (name "unconnected-(PIN_AIN_PWRGND8-Pad2)") (class "Default")
      (node (ref "PIN_AIN_PWRGND8") (pin "2") (pinfunction "2_2") (pintype "passive"))
    )
    (net (code "206") (name "unconnected-(PIN_AIN_PWRGND8-Pad3)") (class "Default")
      (node (ref "PIN_AIN_PWRGND8") (pin "3") (pinfunction "3_3") (pintype "passive"))
    )
    (net (code "207") (name "unconnected-(PIN_AIN_PWRGND8-Pad4)") (class "Default")
      (node (ref "PIN_AIN_PWRGND8") (pin "4") (pinfunction "4_4") (pintype "passive"))
    )
    (net (code "208") (name "unconnected-(PIN_AIN_PWRGND8-Pad5)") (class "Default")
      (node (ref "PIN_AIN_PWRGND8") (pin "5") (pinfunction "5_5") (pintype "passive"))
    )
    (net (code "209") (name "unconnected-(PIN_AIN_PWRGND8-Pad7)") (class "Default")
      (node (ref "PIN_AIN_PWRGND8") (pin "7") (pinfunction "7_7") (pintype "passive"))
    )
    (net (code "210") (name "unconnected-(PIN_AIN_PWRGND8-Pad9)") (class "Default")
      (node (ref "PIN_AIN_PWRGND8") (pin "9") (pinfunction "9_9") (pintype "passive"))
    )
    (net (code "211") (name "unconnected-(PIN_AIN_PWRGND8-Pad11)") (class "Default")
      (node (ref "PIN_AIN_PWRGND8") (pin "11") (pinfunction "11_11") (pintype "passive"))
    )
    (net (code "212") (name "unconnected-(PIN_AIN_PWRGND8-Pad13)") (class "Default")
      (node (ref "PIN_AIN_PWRGND8") (pin "13") (pinfunction "13_13") (pintype "passive"))
    )
    (net (code "213") (name "unconnected-(PIN_AIN_PWRGND9-Pad2)") (class "Default")
      (node (ref "PIN_AIN_PWRGND9") (pin "2") (pinfunction "2_2") (pintype "passive"))
    )
    (net (code "214") (name "unconnected-(PIN_AIN_PWRGND9-Pad3)") (class "Default")
      (node (ref "PIN_AIN_PWRGND9") (pin "3") (pinfunction "3_3") (pintype "passive"))
    )
    (net (code "215") (name "unconnected-(PIN_AIN_PWRGND9-Pad4)") (class "Default")
      (node (ref "PIN_AIN_PWRGND9") (pin "4") (pinfunction "4_4") (pintype "passive"))
    )
    (net (code "216") (name "unconnected-(PIN_AIN_PWRGND9-Pad5)") (class "Default")
      (node (ref "PIN_AIN_PWRGND9") (pin "5") (pinfunction "5_5") (pintype "passive"))
    )
    (net (code "217") (name "unconnected-(PIN_AIN_PWRGND9-Pad7)") (class "Default")
      (node (ref "PIN_AIN_PWRGND9") (pin "7") (pinfunction "7_7") (pintype "passive"))
    )
    (net (code "218") (name "unconnected-(PIN_AIN_PWRGND9-Pad9)") (class "Default")
      (node (ref "PIN_AIN_PWRGND9") (pin "9") (pinfunction "9_9") (pintype "passive"))
    )
    (net (code "219") (name "unconnected-(PIN_AIN_PWRGND9-Pad11)") (class "Default")
      (node (ref "PIN_AIN_PWRGND9") (pin "11") (pinfunction "11_11") (pintype "passive"))
    )
    (net (code "220") (name "unconnected-(PIN_AIN_PWRGND9-Pad13)") (class "Default")
      (node (ref "PIN_AIN_PWRGND9") (pin "13") (pinfunction "13_13") (pintype "passive"))
    )
    (net (code "221") (name "unconnected-(PIN_AIN_PWRGND10-Pad2)") (class "Default")
      (node (ref "PIN_AIN_PWRGND10") (pin "2") (pinfunction "2_2") (pintype "passive"))
    )
    (net (code "222") (name "unconnected-(PIN_AIN_PWRGND10-Pad3)") (class "Default")
      (node (ref "PIN_AIN_PWRGND10") (pin "3") (pinfunction "3_3") (pintype "passive"))
    )
    (net (code "223") (name "unconnected-(PIN_AIN_PWRGND10-Pad4)") (class "Default")
      (node (ref "PIN_AIN_PWRGND10") (pin "4") (pinfunction "4_4") (pintype "passive"))
    )
    (net (code "224") (name "unconnected-(PIN_AIN_PWRGND10-Pad5)") (class "Default")
      (node (ref "PIN_AIN_PWRGND10") (pin "5") (pinfunction "5_5") (pintype "passive"))
    )
    (net (code "225") (name "unconnected-(PIN_AIN_PWRGND10-Pad7)") (class "Default")
      (node (ref "PIN_AIN_PWRGND10") (pin "7") (pinfunction "7_7") (pintype "passive"))
    )
    (net (code "226") (name "unconnected-(PIN_AIN_PWRGND10-Pad9)") (class "Default")
      (node (ref "PIN_AIN_PWRGND10") (pin "9") (pinfunction "9_9") (pintype "passive"))
    )
    (net (code "227") (name "unconnected-(PIN_AIN_PWRGND10-Pad11)") (class "Default")
      (node (ref "PIN_AIN_PWRGND10") (pin "11") (pinfunction "11_11") (pintype "passive"))
    )
    (net (code "228") (name "unconnected-(PIN_AIN_PWRGND10-Pad13)") (class "Default")
      (node (ref "PIN_AIN_PWRGND10") (pin "13") (pinfunction "13_13") (pintype "passive"))
    )
    (net (code "229") (name "unconnected-(PIN_AIN_PWRGND11-Pad2)") (class "Default")
      (node (ref "PIN_AIN_PWRGND11") (pin "2") (pinfunction "2_2") (pintype "passive"))
    )
    (net (code "230") (name "unconnected-(PIN_AIN_PWRGND11-Pad3)") (class "Default")
      (node (ref "PIN_AIN_PWRGND11") (pin "3") (pinfunction "3_3") (pintype "passive"))
    )
    (net (code "231") (name "unconnected-(PIN_AIN_PWRGND11-Pad4)") (class "Default")
      (node (ref "PIN_AIN_PWRGND11") (pin "4") (pinfunction "4_4") (pintype "passive"))
    )
    (net (code "232") (name "unconnected-(PIN_AIN_PWRGND11-Pad5)") (class "Default")
      (node (ref "PIN_AIN_PWRGND11") (pin "5") (pinfunction "5_5") (pintype "passive"))
    )
    (net (code "233") (name "unconnected-(PIN_AIN_PWRGND11-Pad7)") (class "Default")
      (node (ref "PIN_AIN_PWRGND11") (pin "7") (pinfunction "7_7") (pintype "passive"))
    )
    (net (code "234") (name "unconnected-(PIN_AIN_PWRGND11-Pad9)") (class "Default")
      (node (ref "PIN_AIN_PWRGND11") (pin "9") (pinfunction "9_9") (pintype "passive"))
    )
    (net (code "235") (name "unconnected-(PIN_AIN_PWRGND11-Pad11)") (class "Default")
      (node (ref "PIN_AIN_PWRGND11") (pin "11") (pinfunction "11_11") (pintype "passive"))
    )
    (net (code "236") (name "unconnected-(PIN_AIN_PWRGND11-Pad13)") (class "Default")
      (node (ref "PIN_AIN_PWRGND11") (pin "13") (pinfunction "13_13") (pintype "passive"))
    )
    (net (code "237") (name "unconnected-(PIN_AIN_PWRGND12-Pad2)") (class "Default")
      (node (ref "PIN_AIN_PWRGND12") (pin "2") (pinfunction "2_2") (pintype "passive"))
    )
    (net (code "238") (name "unconnected-(PIN_AIN_PWRGND12-Pad3)") (class "Default")
      (node (ref "PIN_AIN_PWRGND12") (pin "3") (pinfunction "3_3") (pintype "passive"))
    )
    (net (code "239") (name "unconnected-(PIN_AIN_PWRGND12-Pad4)") (class "Default")
      (node (ref "PIN_AIN_PWRGND12") (pin "4") (pinfunction "4_4") (pintype "passive"))
    )
    (net (code "240") (name "unconnected-(PIN_AIN_PWRGND12-Pad5)") (class "Default")
      (node (ref "PIN_AIN_PWRGND12") (pin "5") (pinfunction "5_5") (pintype "passive"))
    )
    (net (code "241") (name "unconnected-(PIN_AIN_PWRGND12-Pad7)") (class "Default")
      (node (ref "PIN_AIN_PWRGND12") (pin "7") (pinfunction "7_7") (pintype "passive"))
    )
    (net (code "242") (name "unconnected-(PIN_AIN_PWRGND12-Pad9)") (class "Default")
      (node (ref "PIN_AIN_PWRGND12") (pin "9") (pinfunction "9_9") (pintype "passive"))
    )
    (net (code "243") (name "unconnected-(PIN_AIN_PWRGND12-Pad11)") (class "Default")
      (node (ref "PIN_AIN_PWRGND12") (pin "11") (pinfunction "11_11") (pintype "passive"))
    )
    (net (code "244") (name "unconnected-(PIN_AIN_PWRGND12-Pad13)") (class "Default")
      (node (ref "PIN_AIN_PWRGND12") (pin "13") (pinfunction "13_13") (pintype "passive"))
    )
    (net (code "245") (name "unconnected-(PIN_AIN_PWRGND13-Pad2)") (class "Default")
      (node (ref "PIN_AIN_PWRGND13") (pin "2") (pinfunction "2_2") (pintype "passive"))
    )
    (net (code "246") (name "unconnected-(PIN_AIN_PWRGND13-Pad3)") (class "Default")
      (node (ref "PIN_AIN_PWRGND13") (pin "3") (pinfunction "3_3") (pintype "passive"))
    )
    (net (code "247") (name "unconnected-(PIN_AIN_PWRGND13-Pad4)") (class "Default")
      (node (ref "PIN_AIN_PWRGND13") (pin "4") (pinfunction "4_4") (pintype "passive"))
    )
    (net (code "248") (name "unconnected-(PIN_AIN_PWRGND13-Pad5)") (class "Default")
      (node (ref "PIN_AIN_PWRGND13") (pin "5") (pinfunction "5_5") (pintype "passive"))
    )
    (net (code "249") (name "unconnected-(PIN_AIN_PWRGND13-Pad7)") (class "Default")
      (node (ref "PIN_AIN_PWRGND13") (pin "7") (pinfunction "7_7") (pintype "passive"))
    )
    (net (code "250") (name "unconnected-(PIN_AIN_PWRGND13-Pad9)") (class "Default")
      (node (ref "PIN_AIN_PWRGND13") (pin "9") (pinfunction "9_9") (pintype "passive"))
    )
    (net (code "251") (name "unconnected-(PIN_AIN_PWRGND13-Pad11)") (class "Default")
      (node (ref "PIN_AIN_PWRGND13") (pin "11") (pinfunction "11_11") (pintype "passive"))
    )
    (net (code "252") (name "unconnected-(PIN_AIN_PWRGND13-Pad13)") (class "Default")
      (node (ref "PIN_AIN_PWRGND13") (pin "13") (pinfunction "13_13") (pintype "passive"))
    )
    (net (code "253") (name "unconnected-(PIN_AIN_PWRGND14-Pad2)") (class "Default")
      (node (ref "PIN_AIN_PWRGND14") (pin "2") (pinfunction "2_2") (pintype "passive"))
    )
    (net (code "254") (name "unconnected-(PIN_AIN_PWRGND14-Pad3)") (class "Default")
      (node (ref "PIN_AIN_PWRGND14") (pin "3") (pinfunction "3_3") (pintype "passive"))
    )
    (net (code "255") (name "unconnected-(PIN_AIN_PWRGND14-Pad4)") (class "Default")
      (node (ref "PIN_AIN_PWRGND14") (pin "4") (pinfunction "4_4") (pintype "passive"))
    )
    (net (code "256") (name "unconnected-(PIN_AIN_PWRGND14-Pad5)") (class "Default")
      (node (ref "PIN_AIN_PWRGND14") (pin "5") (pinfunction "5_5") (pintype "passive"))
    )
    (net (code "257") (name "unconnected-(PIN_AIN_PWRGND14-Pad7)") (class "Default")
      (node (ref "PIN_AIN_PWRGND14") (pin "7") (pinfunction "7_7") (pintype "passive"))
    )
    (net (code "258") (name "unconnected-(PIN_AIN_PWRGND14-Pad9)") (class "Default")
      (node (ref "PIN_AIN_PWRGND14") (pin "9") (pinfunction "9_9") (pintype "passive"))
    )
    (net (code "259") (name "unconnected-(PIN_AIN_PWRGND14-Pad11)") (class "Default")
      (node (ref "PIN_AIN_PWRGND14") (pin "11") (pinfunction "11_11") (pintype "passive"))
    )
    (net (code "260") (name "unconnected-(PIN_AIN_PWRGND14-Pad13)") (class "Default")
      (node (ref "PIN_AIN_PWRGND14") (pin "13") (pinfunction "13_13") (pintype "passive"))
    )
    (net (code "261") (name "unconnected-(PIN_AIN_PWRGND15-Pad2)") (class "Default")
      (node (ref "PIN_AIN_PWRGND15") (pin "2") (pinfunction "2_2") (pintype "passive"))
    )
    (net (code "262") (name "unconnected-(PIN_AIN_PWRGND15-Pad3)") (class "Default")
      (node (ref "PIN_AIN_PWRGND15") (pin "3") (pinfunction "3_3") (pintype "passive"))
    )
    (net (code "263") (name "unconnected-(PIN_AIN_PWRGND15-Pad4)") (class "Default")
      (node (ref "PIN_AIN_PWRGND15") (pin "4") (pinfunction "4_4") (pintype "passive"))
    )
    (net (code "264") (name "unconnected-(PIN_AIN_PWRGND15-Pad5)") (class "Default")
      (node (ref "PIN_AIN_PWRGND15") (pin "5") (pinfunction "5_5") (pintype "passive"))
    )
    (net (code "265") (name "unconnected-(PIN_AIN_PWRGND15-Pad7)") (class "Default")
      (node (ref "PIN_AIN_PWRGND15") (pin "7") (pinfunction "7_7") (pintype "passive"))
    )
    (net (code "266") (name "unconnected-(PIN_AIN_PWRGND15-Pad9)") (class "Default")
      (node (ref "PIN_AIN_PWRGND15") (pin "9") (pinfunction "9_9") (pintype "passive"))
    )
    (net (code "267") (name "unconnected-(PIN_AIN_PWRGND15-Pad11)") (class "Default")
      (node (ref "PIN_AIN_PWRGND15") (pin "11") (pinfunction "11_11") (pintype "passive"))
    )
    (net (code "268") (name "unconnected-(PIN_AIN_PWRGND15-Pad13)") (class "Default")
      (node (ref "PIN_AIN_PWRGND15") (pin "13") (pinfunction "13_13") (pintype "passive"))
    )
    (net (code "269") (name "unconnected-(PIN_AIN_PWRGND16-Pad2)") (class "Default")
      (node (ref "PIN_AIN_PWRGND16") (pin "2") (pinfunction "2_2") (pintype "passive"))
    )
    (net (code "270") (name "unconnected-(PIN_AIN_PWRGND16-Pad3)") (class "Default")
      (node (ref "PIN_AIN_PWRGND16") (pin "3") (pinfunction "3_3") (pintype "passive"))
    )
    (net (code "271") (name "unconnected-(PIN_AIN_PWRGND16-Pad4)") (class "Default")
      (node (ref "PIN_AIN_PWRGND16") (pin "4") (pinfunction "4_4") (pintype "passive"))
    )
    (net (code "272") (name "unconnected-(PIN_AIN_PWRGND16-Pad5)") (class "Default")
      (node (ref "PIN_AIN_PWRGND16") (pin "5") (pinfunction "5_5") (pintype "passive"))
    )
    (net (code "273") (name "unconnected-(PIN_AIN_PWRGND16-Pad7)") (class "Default")
      (node (ref "PIN_AIN_PWRGND16") (pin "7") (pinfunction "7_7") (pintype "passive"))
    )
    (net (code "274") (name "unconnected-(PIN_AIN_PWRGND16-Pad9)") (class "Default")
      (node (ref "PIN_AIN_PWRGND16") (pin "9") (pinfunction "9_9") (pintype "passive"))
    )
    (net (code "275") (name "unconnected-(PIN_AIN_PWRGND16-Pad11)") (class "Default")
      (node (ref "PIN_AIN_PWRGND16") (pin "11") (pinfunction "11_11") (pintype "passive"))
    )
    (net (code "276") (name "unconnected-(PIN_AIN_PWRGND16-Pad13)") (class "Default")
      (node (ref "PIN_AIN_PWRGND16") (pin "13") (pinfunction "13_13") (pintype "passive"))
    )
    (net (code "277") (name "unconnected-(PIN_AIN_PWRGND17-Pad2)") (class "Default")
      (node (ref "PIN_AIN_PWRGND17") (pin "2") (pinfunction "2_2") (pintype "passive"))
    )
    (net (code "278") (name "unconnected-(PIN_AIN_PWRGND17-Pad3)") (class "Default")
      (node (ref "PIN_AIN_PWRGND17") (pin "3") (pinfunction "3_3") (pintype "passive"))
    )
    (net (code "279") (name "unconnected-(PIN_AIN_PWRGND17-Pad4)") (class "Default")
      (node (ref "PIN_AIN_PWRGND17") (pin "4") (pinfunction "4_4") (pintype "passive"))
    )
    (net (code "280") (name "unconnected-(PIN_AIN_PWRGND17-Pad5)") (class "Default")
      (node (ref "PIN_AIN_PWRGND17") (pin "5") (pinfunction "5_5") (pintype "passive"))
    )
    (net (code "281") (name "unconnected-(PIN_AIN_PWRGND17-Pad7)") (class "Default")
      (node (ref "PIN_AIN_PWRGND17") (pin "7") (pinfunction "7_7") (pintype "passive"))
    )
    (net (code "282") (name "unconnected-(PIN_AIN_PWRGND17-Pad9)") (class "Default")
      (node (ref "PIN_AIN_PWRGND17") (pin "9") (pinfunction "9_9") (pintype "passive"))
    )
    (net (code "283") (name "unconnected-(PIN_AIN_PWRGND17-Pad11)") (class "Default")
      (node (ref "PIN_AIN_PWRGND17") (pin "11") (pinfunction "11_11") (pintype "passive"))
    )
    (net (code "284") (name "unconnected-(PIN_AIN_PWRGND17-Pad13)") (class "Default")
      (node (ref "PIN_AIN_PWRGND17") (pin "13") (pinfunction "13_13") (pintype "passive"))
    )
    (net (code "285") (name "unconnected-(PIN_AIN_PWRGND18-Pad2)") (class "Default")
      (node (ref "PIN_AIN_PWRGND18") (pin "2") (pinfunction "2_2") (pintype "passive"))
    )
    (net (code "286") (name "unconnected-(PIN_AIN_PWRGND18-Pad3)") (class "Default")
      (node (ref "PIN_AIN_PWRGND18") (pin "3") (pinfunction "3_3") (pintype "passive"))
    )
    (net (code "287") (name "unconnected-(PIN_AIN_PWRGND18-Pad4)") (class "Default")
      (node (ref "PIN_AIN_PWRGND18") (pin "4") (pinfunction "4_4") (pintype "passive"))
    )
    (net (code "288") (name "unconnected-(PIN_AIN_PWRGND18-Pad5)") (class "Default")
      (node (ref "PIN_AIN_PWRGND18") (pin "5") (pinfunction "5_5") (pintype "passive"))
    )
    (net (code "289") (name "unconnected-(PIN_AIN_PWRGND18-Pad7)") (class "Default")
      (node (ref "PIN_AIN_PWRGND18") (pin "7") (pinfunction "7_7") (pintype "passive"))
    )
    (net (code "290") (name "unconnected-(PIN_AIN_PWRGND18-Pad9)") (class "Default")
      (node (ref "PIN_AIN_PWRGND18") (pin "9") (pinfunction "9_9") (pintype "passive"))
    )
    (net (code "291") (name "unconnected-(PIN_AIN_PWRGND18-Pad11)") (class "Default")
      (node (ref "PIN_AIN_PWRGND18") (pin "11") (pinfunction "11_11") (pintype "passive"))
    )
    (net (code "292") (name "unconnected-(PIN_AIN_PWRGND18-Pad13)") (class "Default")
      (node (ref "PIN_AIN_PWRGND18") (pin "13") (pinfunction "13_13") (pintype "passive"))
    )
    (net (code "293") (name "unconnected-(PIN_AIN_PWRGND19-Pad2)") (class "Default")
      (node (ref "PIN_AIN_PWRGND19") (pin "2") (pinfunction "2_2") (pintype "passive"))
    )
    (net (code "294") (name "unconnected-(PIN_AIN_PWRGND19-Pad3)") (class "Default")
      (node (ref "PIN_AIN_PWRGND19") (pin "3") (pinfunction "3_3") (pintype "passive"))
    )
    (net (code "295") (name "unconnected-(PIN_AIN_PWRGND19-Pad4)") (class "Default")
      (node (ref "PIN_AIN_PWRGND19") (pin "4") (pinfunction "4_4") (pintype "passive"))
    )
    (net (code "296") (name "unconnected-(PIN_AIN_PWRGND19-Pad5)") (class "Default")
      (node (ref "PIN_AIN_PWRGND19") (pin "5") (pinfunction "5_5") (pintype "passive"))
    )
    (net (code "297") (name "unconnected-(PIN_AIN_PWRGND19-Pad7)") (class "Default")
      (node (ref "PIN_AIN_PWRGND19") (pin "7") (pinfunction "7_7") (pintype "passive"))
    )
    (net (code "298") (name "unconnected-(PIN_AIN_PWRGND19-Pad9)") (class "Default")
      (node (ref "PIN_AIN_PWRGND19") (pin "9") (pinfunction "9_9") (pintype "passive"))
    )
    (net (code "299") (name "unconnected-(PIN_AIN_PWRGND19-Pad11)") (class "Default")
      (node (ref "PIN_AIN_PWRGND19") (pin "11") (pinfunction "11_11") (pintype "passive"))
    )
    (net (code "300") (name "unconnected-(PIN_AIN_PWRGND19-Pad13)") (class "Default")
      (node (ref "PIN_AIN_PWRGND19") (pin "13") (pinfunction "13_13") (pintype "passive"))
    )
    (net (code "301") (name "unconnected-(PIN_AIN_PWRGND20-Pad2)") (class "Default")
      (node (ref "PIN_AIN_PWRGND20") (pin "2") (pinfunction "2_2") (pintype "passive"))
    )
    (net (code "302") (name "unconnected-(PIN_AIN_PWRGND20-Pad3)") (class "Default")
      (node (ref "PIN_AIN_PWRGND20") (pin "3") (pinfunction "3_3") (pintype "passive"))
    )
    (net (code "303") (name "unconnected-(PIN_AIN_PWRGND20-Pad4)") (class "Default")
      (node (ref "PIN_AIN_PWRGND20") (pin "4") (pinfunction "4_4") (pintype "passive"))
    )
    (net (code "304") (name "unconnected-(PIN_AIN_PWRGND20-Pad5)") (class "Default")
      (node (ref "PIN_AIN_PWRGND20") (pin "5") (pinfunction "5_5") (pintype "passive"))
    )
    (net (code "305") (name "unconnected-(PIN_AIN_PWRGND20-Pad7)") (class "Default")
      (node (ref "PIN_AIN_PWRGND20") (pin "7") (pinfunction "7_7") (pintype "passive"))
    )
    (net (code "306") (name "unconnected-(PIN_AIN_PWRGND20-Pad9)") (class "Default")
      (node (ref "PIN_AIN_PWRGND20") (pin "9") (pinfunction "9_9") (pintype "passive"))
    )
    (net (code "307") (name "unconnected-(PIN_AIN_PWRGND20-Pad11)") (class "Default")
      (node (ref "PIN_AIN_PWRGND20") (pin "11") (pinfunction "11_11") (pintype "passive"))
    )
    (net (code "308") (name "unconnected-(PIN_AIN_PWRGND20-Pad13)") (class "Default")
      (node (ref "PIN_AIN_PWRGND20") (pin "13") (pinfunction "13_13") (pintype "passive"))
    )
  )
)
